# EEZ_DIB_MCU_r2B3.net
KiCad netlist of a schematic drawn in EAGLE
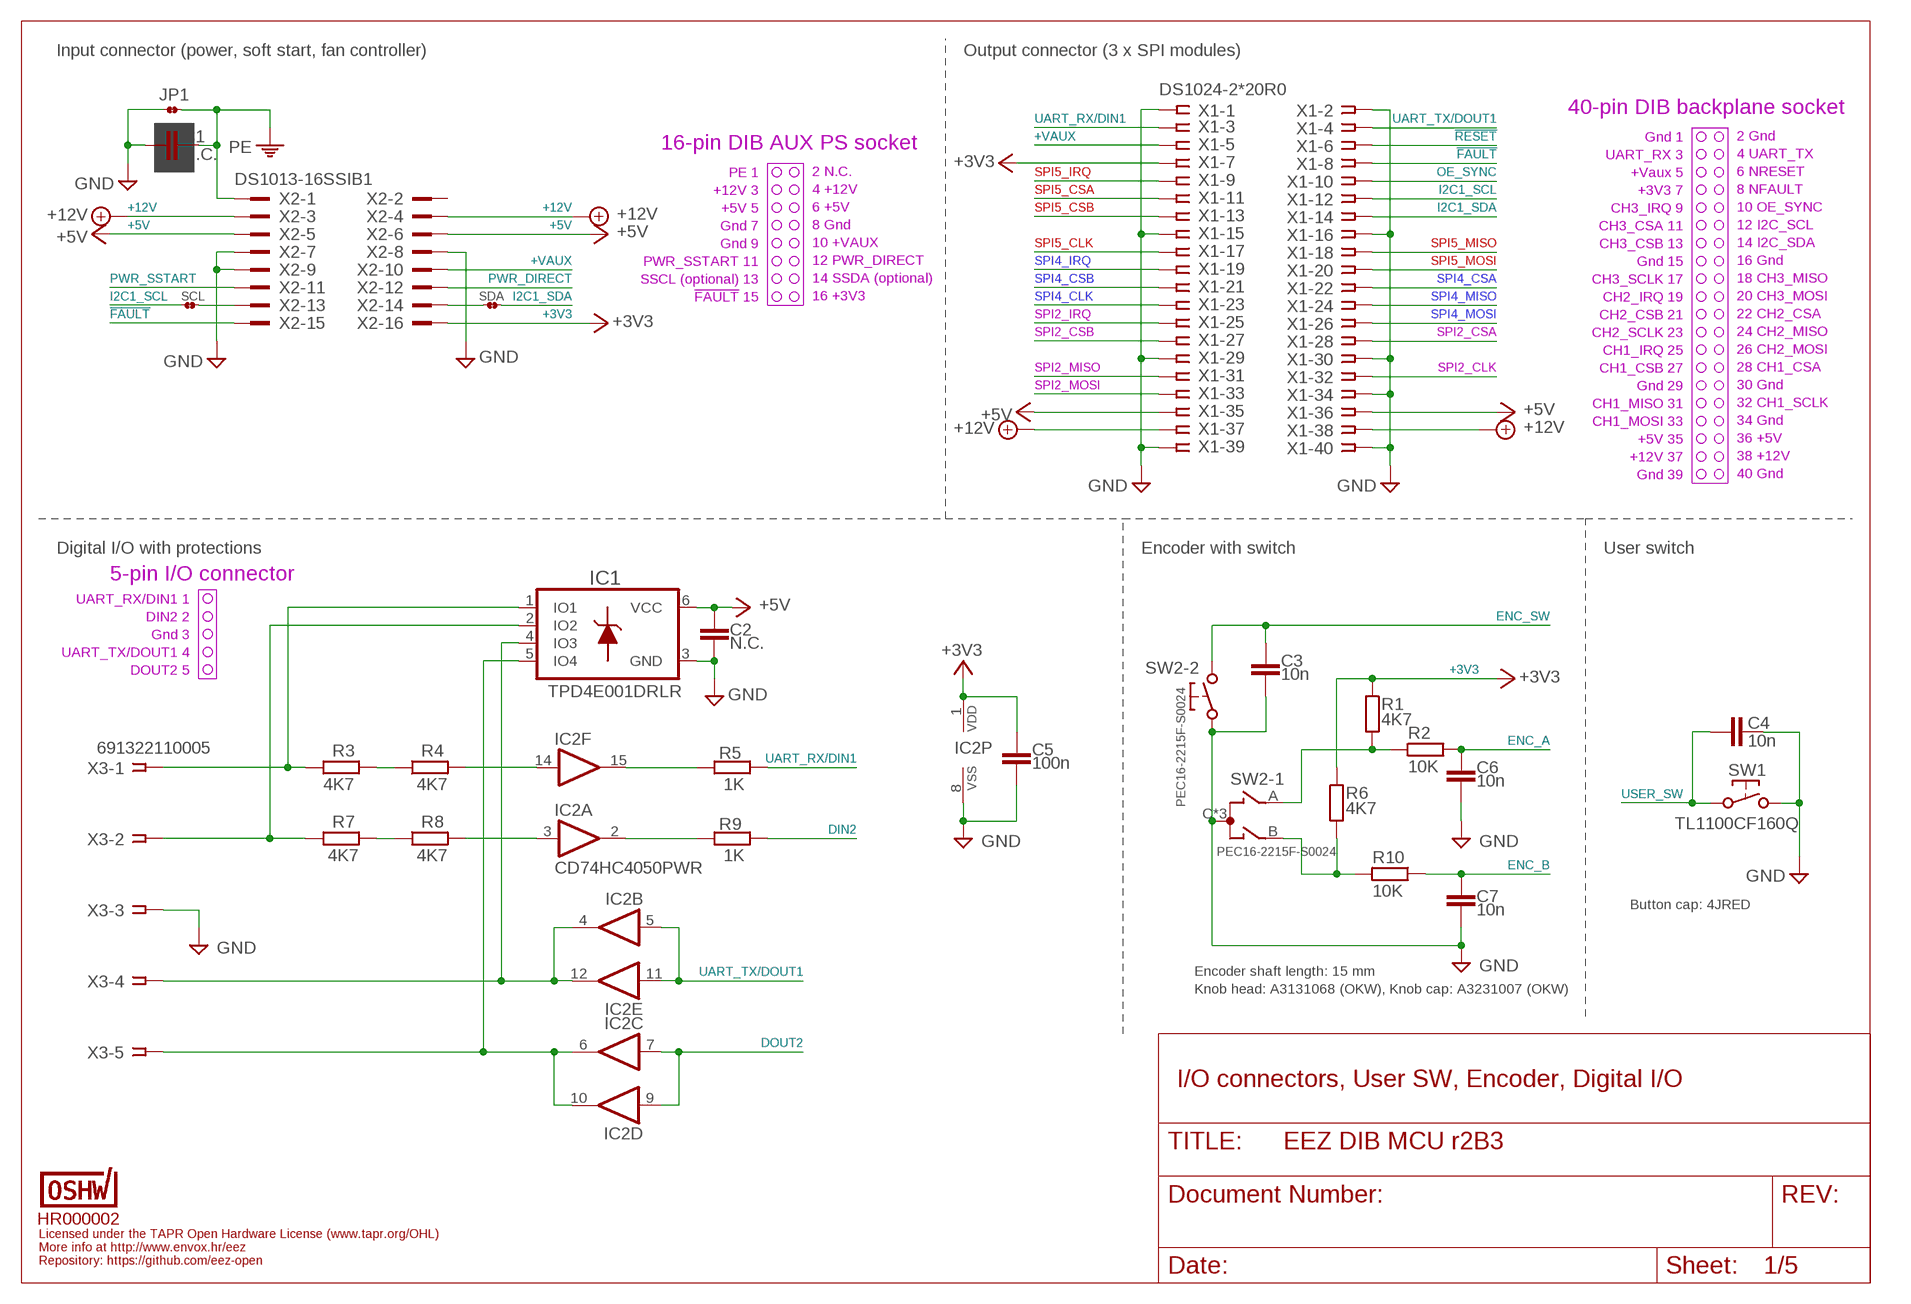
[diagram p0: schematic, sheet 1]
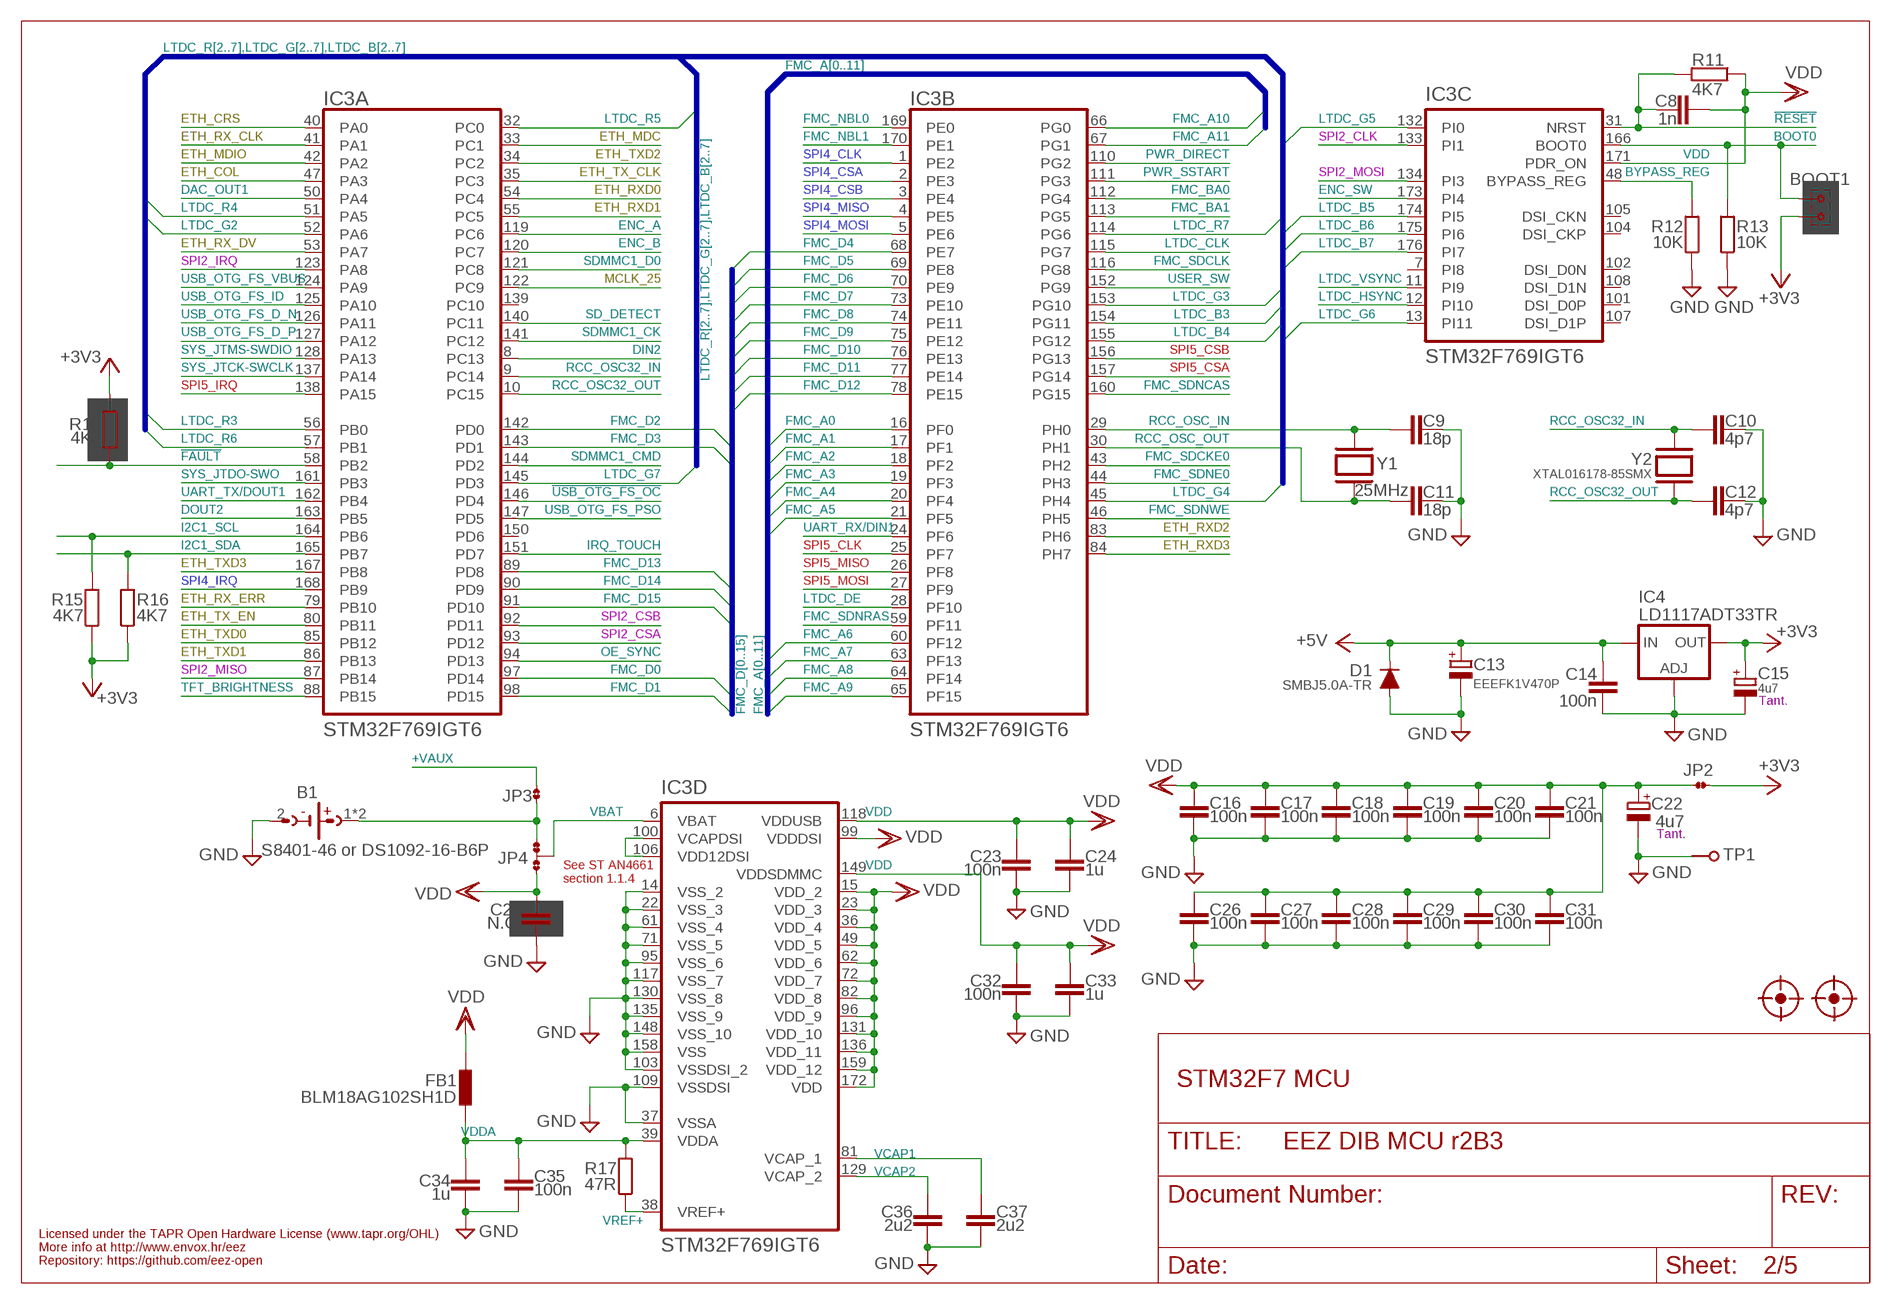
[diagram p1: schematic, sheet 2]
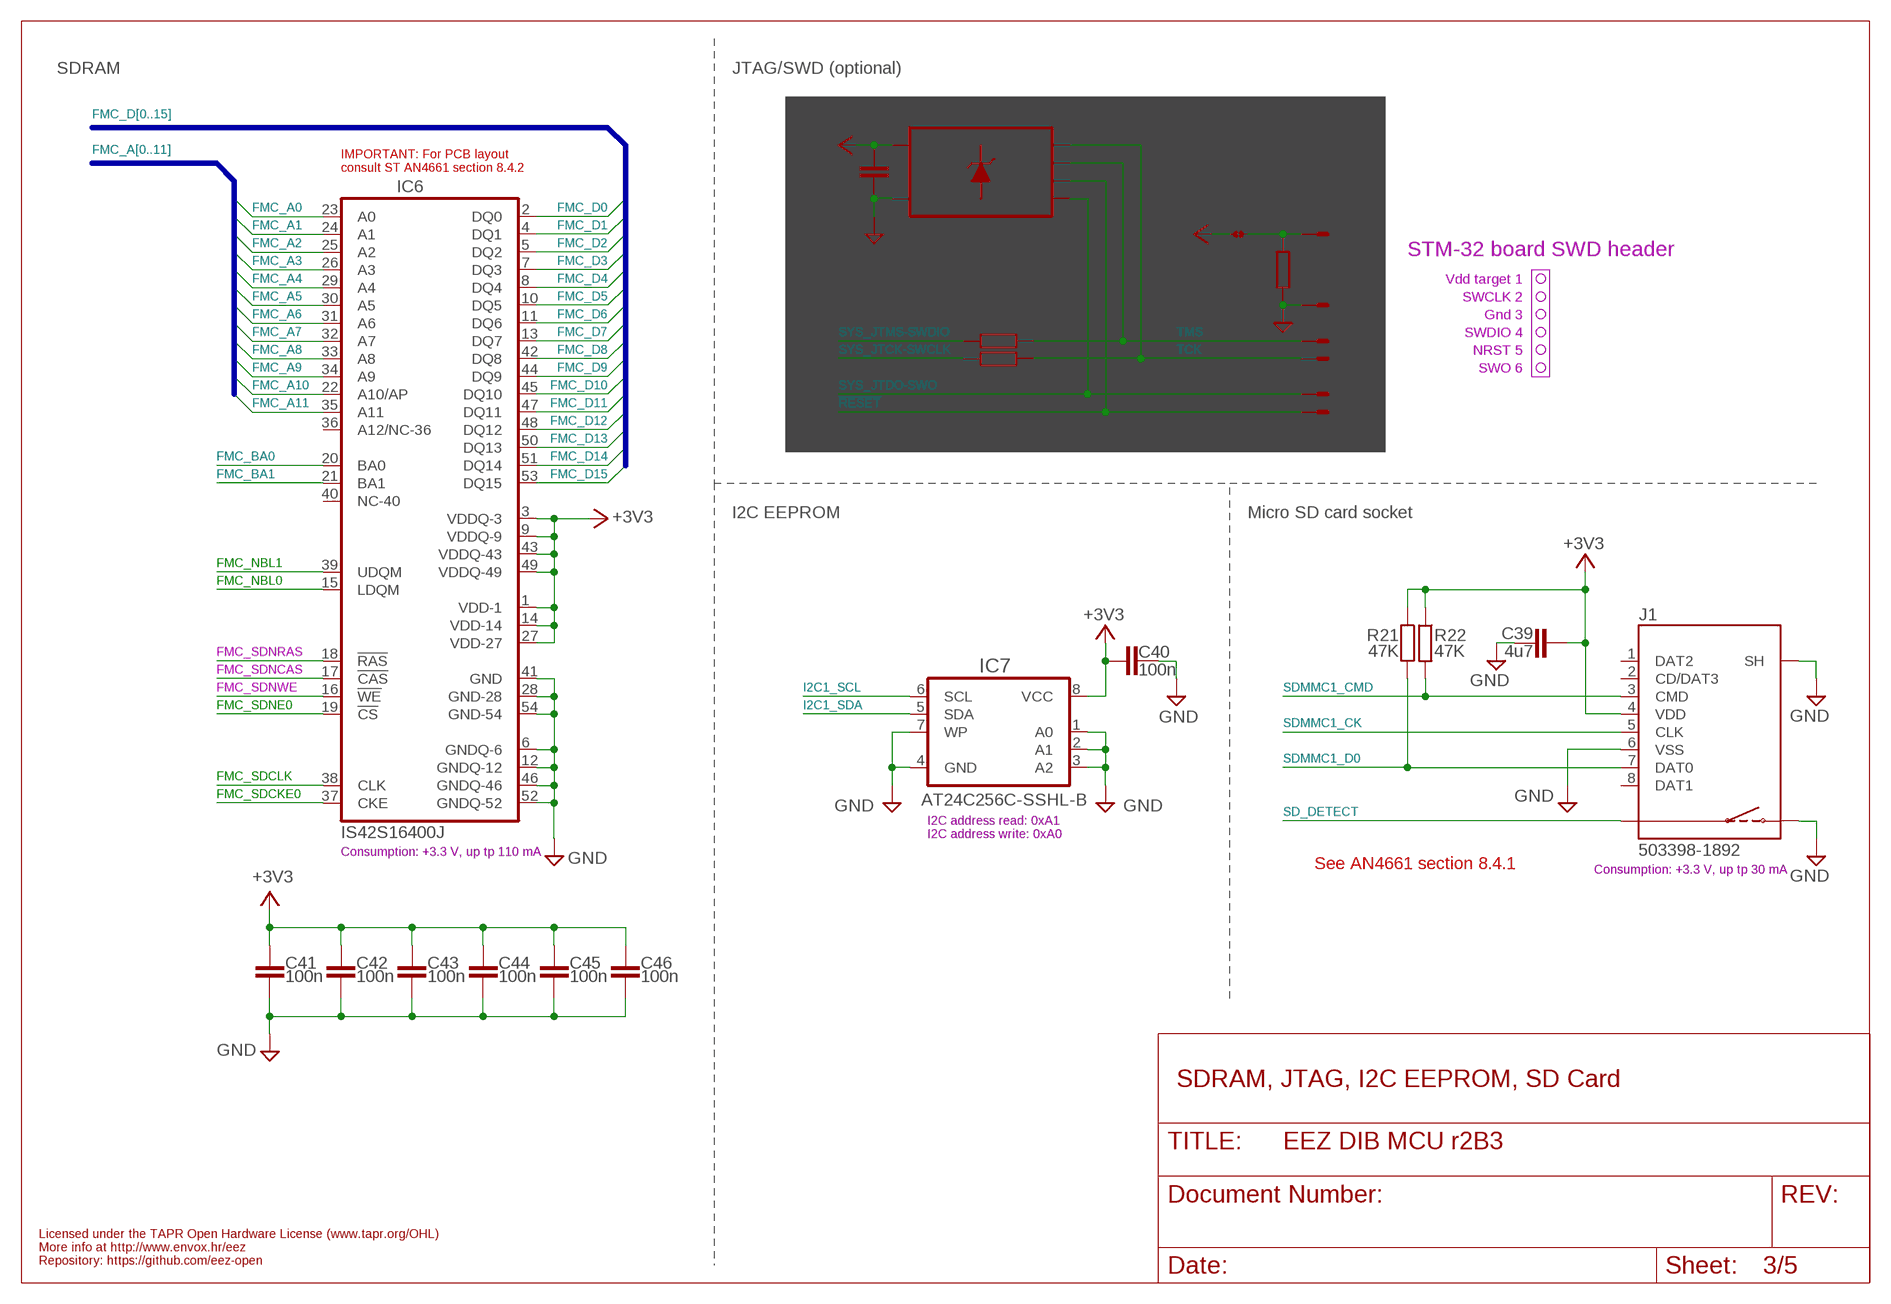
[diagram p2: schematic, sheet 3]
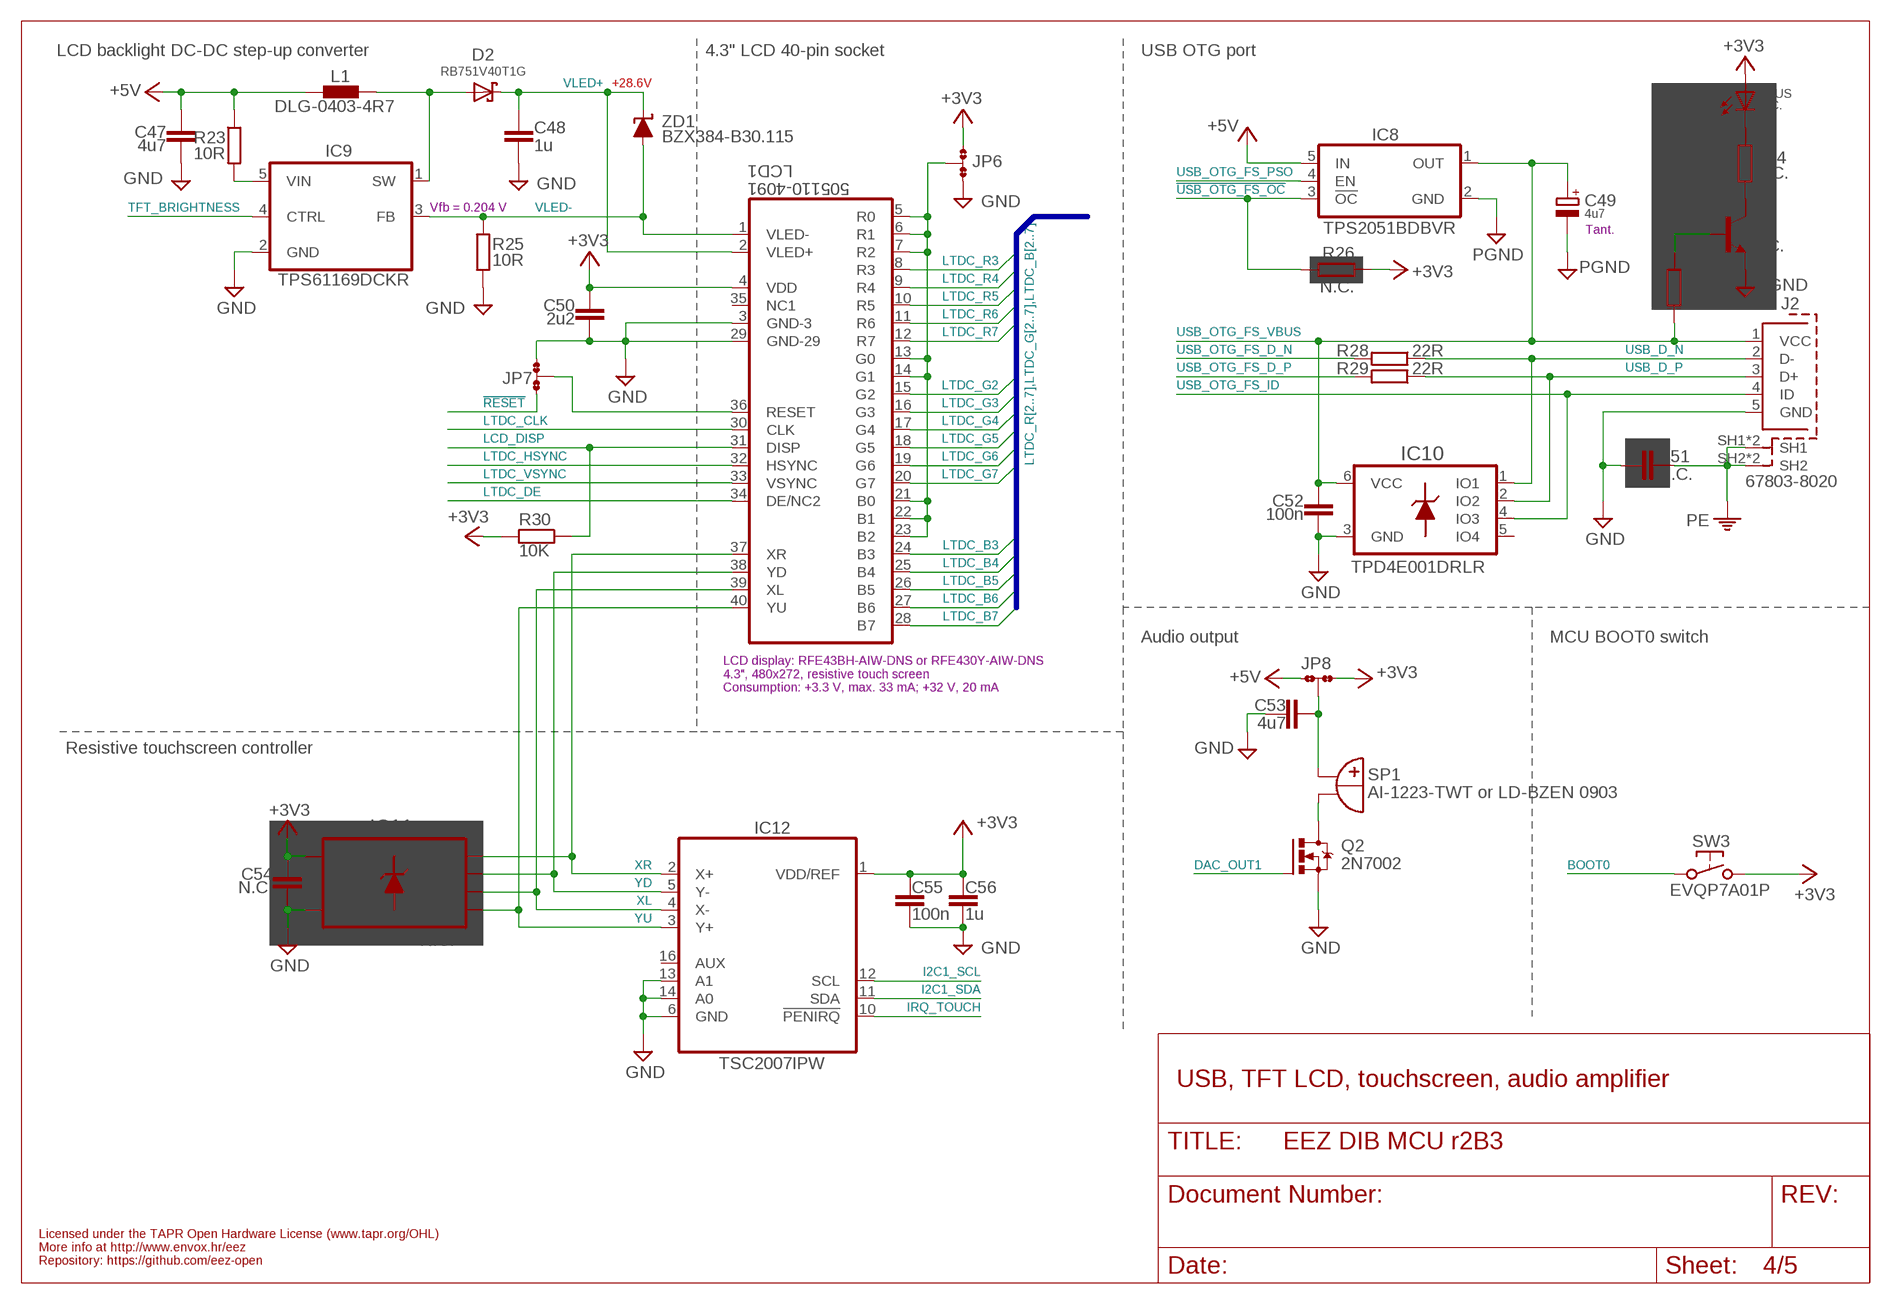
[diagram p3: schematic, sheet 4]
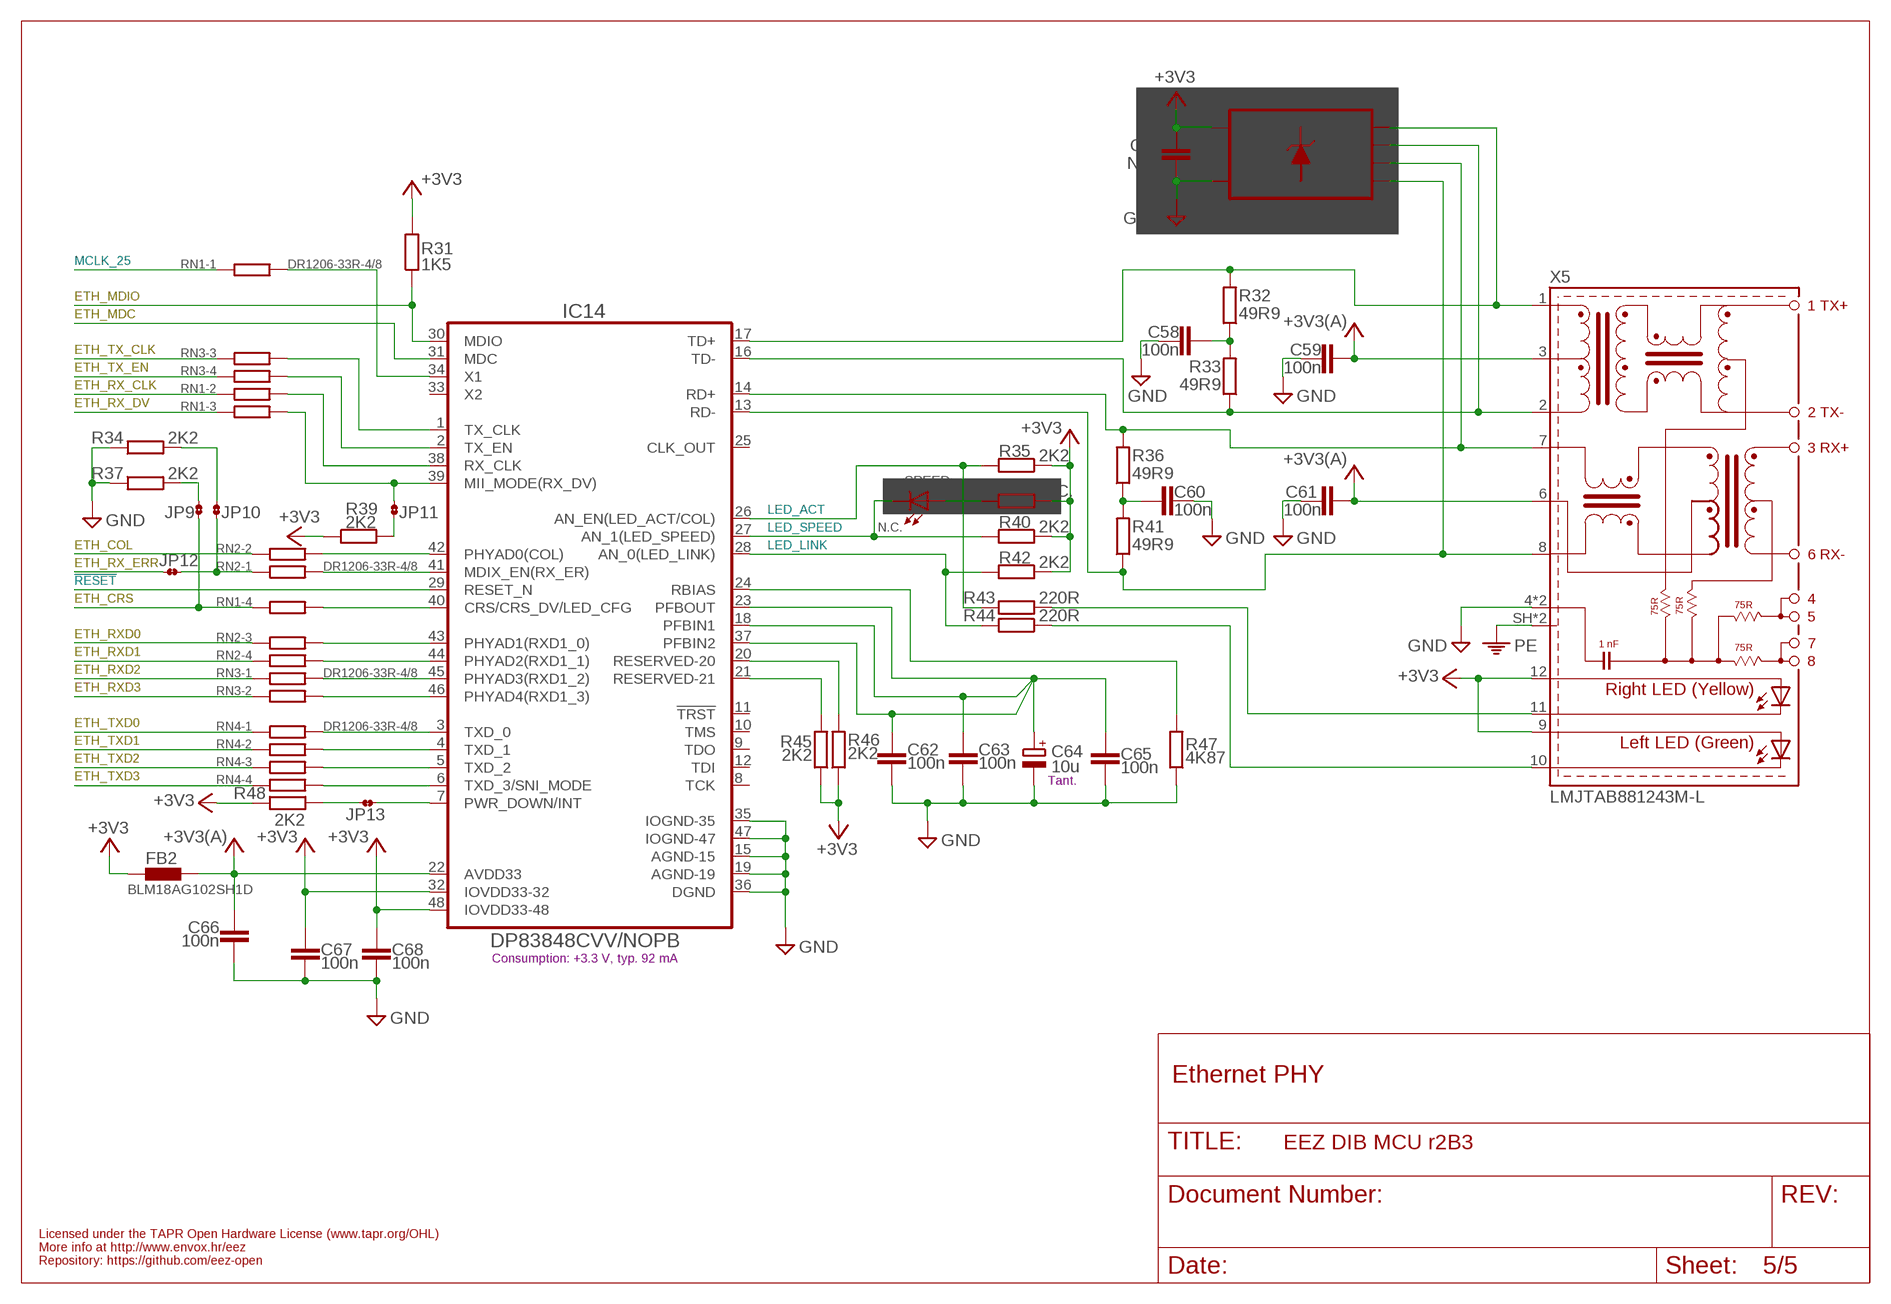
[diagram p4: schematic, sheet 5]

(export (version "E")
  (design (tool "Eeschema 10.0.6"))
  (components
    (comp (ref "C47")
      (value "4u7")
      (footprint "eagle-import:C1206")
      (libsource (lib "eagle-import") (part "C-EUC1206"))
    )
    (comp (ref "C48")
      (value "1u")
      (footprint "eagle-import:C0805")
      (libsource (lib "eagle-import") (part "C-EUC0805"))
    )
    (comp (ref "C49")
      (value "4u7")
      (footprint "eagle-import:EC1206")
      (libsource (lib "eagle-import") (part "ECAP1206"))
    )
    (comp (ref "C50")
      (value "2u2")
      (footprint "eagle-import:C0805")
      (libsource (lib "eagle-import") (part "C-EUC0805"))
    )
    (comp (ref "C51")
      (value "N.C.")
      (footprint "eagle-import:C0805")
      (libsource (lib "eagle-import") (part "C-EUC0805"))
    )
    (comp (ref "C52")
      (value "100n")
      (footprint "eagle-import:C0603")
      (libsource (lib "eagle-import") (part "C-EUC0603"))
    )
    (comp (ref "C53")
      (value "4u7")
      (footprint "eagle-import:C1206")
      (libsource (lib "eagle-import") (part "C-EUC1206"))
    )
    (comp (ref "C54")
      (value "N.C.")
      (footprint "eagle-import:C0603")
      (libsource (lib "eagle-import") (part "C-EUC0603"))
    )
    (comp (ref "C55")
      (value "100n")
      (footprint "eagle-import:C0603")
      (libsource (lib "eagle-import") (part "C-EUC0603"))
    )
    (comp (ref "C56")
      (value "1u")
      (footprint "eagle-import:C0805")
      (libsource (lib "eagle-import") (part "C-EUC0805"))
    )
    (comp (ref "D2")
      (value "RB751V40T1G")
      (footprint "eagle-import:SOD323-R")
      (libsource (lib "eagle-import") (part "SCHOTTKYSOD-323R"))
    )
    (comp (ref "IC8")
      (value "TPS2051BDBVR")
      (footprint "eagle-import:DBV5")
      (libsource (lib "eagle-import") (part "TPS2051B"))
    )
    (comp (ref "IC9")
      (value "TPS61169DCKR")
      (footprint "eagle-import:DCK5")
      (fields (field (name "MANUFACTURER") "Texas Instruments"))
      (libsource (lib "eagle-import") (part "TPS61169DCKR"))
    )
    (comp (ref "IC10")
      (value "TPD4E001DRLR")
      (footprint "eagle-import:DRL6")
      (libsource (lib "eagle-import") (part "TPD4E001-DRL"))
    )
    (comp (ref "IC11")
      (value "N.C.")
      (footprint "eagle-import:DRL6")
      (libsource (lib "eagle-import") (part "TPD4E001-DRL"))
    )
    (comp (ref "IC12")
      (value "TSC2007IPW")
      (footprint "eagle-import:PW(R-PDSO-G16)")
      (libsource (lib "eagle-import") (part "TSC2007IPW"))
    )
    (comp (ref "J2")
      (value "67803-8020")
      (footprint "eagle-import:678038020")
      (libsource (lib "eagle-import") (part "678038020"))
    )
    (comp (ref "JP6")
      (value "JP3-CUT")
      (footprint "eagle-import:JP3-CUT")
      (libsource (lib "eagle-import") (part "JP3-CUT"))
    )
    (comp (ref "JP7")
      (value "JP3-CUT")
      (footprint "eagle-import:JP3-CUT")
      (libsource (lib "eagle-import") (part "JP3-CUT"))
    )
    (comp (ref "JP8")
      (value "JP3-CUT")
      (footprint "eagle-import:JP3-CUT")
      (libsource (lib "eagle-import") (part "JP3-CUT"))
    )
    (comp (ref "L1")
      (value "DLG-0403-4R7")
      (footprint "eagle-import:DE0403")
      (libsource (lib "eagle-import") (part "DE0403"))
    )
    (comp (ref "LCD1")
      (value "505110-4091")
      (footprint "eagle-import:FPC_40")
      (libsource (lib "eagle-import") (part "RFE430Y-AIW-DNS"))
    )
    (comp (ref "Q1")
      (value "N.C.")
      (footprint "eagle-import:SOT23-BEC")
      (libsource (lib "eagle-import") (part "-NPN-SOT23-BECMMBT5551LT1"))
    )
    (comp (ref "Q2")
      (value "2N7002")
      (footprint "eagle-import:SOT103P240X110-3N")
      (fields (field (name "MPN") "2N7002-7-F"))
      (libsource (lib "eagle-import") (part "2N7002"))
    )
    (comp (ref "R23")
      (value "10R")
      (footprint "eagle-import:R0805")
      (libsource (lib "eagle-import") (part "R-EU_R0805"))
    )
    (comp (ref "R24")
      (value "N.C.")
      (footprint "eagle-import:R0805")
      (libsource (lib "eagle-import") (part "R-EU_R0805"))
    )
    (comp (ref "R25")
      (value "10R")
      (footprint "eagle-import:R0805")
      (libsource (lib "eagle-import") (part "R-EU_R0805"))
    )
    (comp (ref "R26")
      (value "N.C.")
      (footprint "eagle-import:R0805")
      (libsource (lib "eagle-import") (part "R-EU_R0805"))
    )
    (comp (ref "R27")
      (value "N.C.")
      (footprint "eagle-import:R0805")
      (libsource (lib "eagle-import") (part "R-EU_R0805"))
    )
    (comp (ref "R28")
      (value "22R")
      (footprint "eagle-import:R0805")
      (libsource (lib "eagle-import") (part "R-EU_R0805"))
    )
    (comp (ref "R29")
      (value "22R")
      (footprint "eagle-import:R0805")
      (libsource (lib "eagle-import") (part "R-EU_R0805"))
    )
    (comp (ref "R30")
      (value "10K")
      (footprint "eagle-import:R0805")
      (libsource (lib "eagle-import") (part "R-EU_R0805"))
    )
    (comp (ref "SP1")
      (value "AI-1223-TWT or LD-BZEN 0903")
      (footprint "eagle-import:AI-1223-TWT_COMBO")
      (libsource (lib "eagle-import") (part "AI-1223-TWT-LDB0903"))
    )
    (comp (ref "SW3")
      (value "EVQP7A01P")
      (footprint "eagle-import:PANASONIC_EVQP")
      (libsource (lib "eagle-import") (part "EVQP7A01P"))
    )
    (comp (ref "VBUS")
      (value "N.C.")
      (footprint "eagle-import:LED_0805")
      (libsource (lib "eagle-import") (part "LED0805"))
    )
    (comp (ref "ZD1")
      (value "BZX384-B30.115")
      (footprint "eagle-import:SOD323-W")
      (libsource (lib "eagle-import") (part "ZENER-DIODESOD323"))
    )
    (comp (ref "C1")
      (value "N.C.")
      (footprint "eagle-import:C0805")
      (libsource (lib "eagle-import") (part "C-EUC0805"))
    )
    (comp (ref "C2")
      (value "N.C.")
      (footprint "eagle-import:C0603")
      (libsource (lib "eagle-import") (part "C-EUC0603"))
    )
    (comp (ref "C3")
      (value "10n")
      (footprint "eagle-import:C0805")
      (libsource (lib "eagle-import") (part "C-EUC0805"))
    )
    (comp (ref "C4")
      (value "10n")
      (footprint "eagle-import:C0805")
      (libsource (lib "eagle-import") (part "C-EUC0805"))
    )
    (comp (ref "C5")
      (value "100n")
      (footprint "eagle-import:C0603")
      (libsource (lib "eagle-import") (part "C-EUC0603"))
    )
    (comp (ref "C6")
      (value "10n")
      (footprint "eagle-import:C0805")
      (libsource (lib "eagle-import") (part "C-EUC0805"))
    )
    (comp (ref "C7")
      (value "10n")
      (footprint "eagle-import:C0805")
      (libsource (lib "eagle-import") (part "C-EUC0805"))
    )
    (comp (ref "IC1")
      (value "TPD4E001DRLR")
      (footprint "eagle-import:DRL6")
      (libsource (lib "eagle-import") (part "TPD4E001-DRL"))
    )
    (comp (ref "IC2")
      (value "CD74HC4050PWR")
      (footprint "eagle-import:PW16")
      (libsource (lib "eagle-import") (part "CD74HC4050PWR"))
    )
    (comp (ref "JP1")
      (value "JP2-NOCUT")
      (footprint "eagle-import:JP2-NOCUT")
      (libsource (lib "eagle-import") (part "JP2-NOCUT"))
    )
    (comp (ref "R1")
      (value "4K7")
      (footprint "eagle-import:R0805")
      (libsource (lib "eagle-import") (part "R-EU_R0805"))
    )
    (comp (ref "R2")
      (value "10K")
      (footprint "eagle-import:R0805")
      (libsource (lib "eagle-import") (part "R-EU_R0805"))
    )
    (comp (ref "R3")
      (value "4K7")
      (footprint "eagle-import:R0805")
      (libsource (lib "eagle-import") (part "R-EU_R0805"))
    )
    (comp (ref "R4")
      (value "4K7")
      (footprint "eagle-import:R0805")
      (libsource (lib "eagle-import") (part "R-EU_R0805"))
    )
    (comp (ref "R5")
      (value "1K")
      (footprint "eagle-import:R0805")
      (libsource (lib "eagle-import") (part "R-EU_R0805"))
    )
    (comp (ref "R6")
      (value "4K7")
      (footprint "eagle-import:R0805")
      (libsource (lib "eagle-import") (part "R-EU_R0805"))
    )
    (comp (ref "R7")
      (value "4K7")
      (footprint "eagle-import:R0805")
      (libsource (lib "eagle-import") (part "R-EU_R0805"))
    )
    (comp (ref "R8")
      (value "4K7")
      (footprint "eagle-import:R0805")
      (libsource (lib "eagle-import") (part "R-EU_R0805"))
    )
    (comp (ref "R9")
      (value "1K")
      (footprint "eagle-import:R0805")
      (libsource (lib "eagle-import") (part "R-EU_R0805"))
    )
    (comp (ref "R10")
      (value "10K")
      (footprint "eagle-import:R0805")
      (libsource (lib "eagle-import") (part "R-EU_R0805"))
    )
    (comp (ref "SCL")
      (value "JP2-NOCUT")
      (footprint "eagle-import:JP2-NOCUT")
      (libsource (lib "eagle-import") (part "JP2-NOCUT"))
    )
    (comp (ref "SDA")
      (value "JP2-NOCUT")
      (footprint "eagle-import:JP2-NOCUT")
      (libsource (lib "eagle-import") (part "JP2-NOCUT"))
    )
    (comp (ref "SW1")
      (value "TL1100CF160Q")
      (footprint "eagle-import:TL1100C")
      (libsource (lib "eagle-import") (part "TL1100C"))
    )
    (comp (ref "SW2")
      (value "PEC16-2215F-S0024")
      (footprint "eagle-import:PEC16-2215F")
      (libsource (lib "eagle-import") (part "ENCODER_SW-PEC16"))
    )
    (comp (ref "U$3")
      (value "HR000002")
      (footprint "eagle-import:CERT-SMALL-SILK")
      (libsource (lib "eagle-import") (part "CERT-SMALL"))
    )
    (comp (ref "X1")
      (value "DS1024-2*20R0")
      (footprint "eagle-import:ZL263-40DG")
      (libsource (lib "eagle-import") (part "ZL263-40DG"))
    )
    (comp (ref "X2")
      (value "DS1013-16SSIB1")
      (footprint "eagle-import:IDC-16PIN")
      (libsource (lib "eagle-import") (part "IDC-16PIN"))
    )
    (comp (ref "X3")
      (value "691322110005")
      (footprint "eagle-import:MC1,5_5-G-3,5")
      (libsource (lib "eagle-import") (part "MC1,5/5-G-3,5"))
    )
    (comp (ref "C38")
      (value "N.C.")
      (footprint "eagle-import:C0603")
      (libsource (lib "eagle-import") (part "C-EUC0603"))
    )
    (comp (ref "C39")
      (value "4u7")
      (footprint "eagle-import:C1206")
      (libsource (lib "eagle-import") (part "C-EUC1206"))
    )
    (comp (ref "C40")
      (value "100n")
      (footprint "eagle-import:C0603")
      (libsource (lib "eagle-import") (part "C-EUC0603"))
    )
    (comp (ref "C41")
      (value "100n")
      (footprint "eagle-import:C0603")
      (libsource (lib "eagle-import") (part "C-EUC0603"))
    )
    (comp (ref "C42")
      (value "100n")
      (footprint "eagle-import:C0603")
      (libsource (lib "eagle-import") (part "C-EUC0603"))
    )
    (comp (ref "C43")
      (value "100n")
      (footprint "eagle-import:C0603")
      (libsource (lib "eagle-import") (part "C-EUC0603"))
    )
    (comp (ref "C44")
      (value "100n")
      (footprint "eagle-import:C0603")
      (libsource (lib "eagle-import") (part "C-EUC0603"))
    )
    (comp (ref "C45")
      (value "100n")
      (footprint "eagle-import:C0603")
      (libsource (lib "eagle-import") (part "C-EUC0603"))
    )
    (comp (ref "C46")
      (value "100n")
      (footprint "eagle-import:C0603")
      (libsource (lib "eagle-import") (part "C-EUC0603"))
    )
    (comp (ref "IC5")
      (value "N.C.")
      (footprint "eagle-import:DRL6")
      (libsource (lib "eagle-import") (part "TPD4E001-DRL"))
    )
    (comp (ref "IC6")
      (value "IS42S16400J")
      (footprint "eagle-import:TSOPII-54")
      (libsource (lib "eagle-import") (part "IS42S16400"))
    )
    (comp (ref "IC7")
      (value "AT24C256C-SSHL-B")
      (footprint "eagle-import:SOIC127P600X173-8N")
      (libsource (lib "eagle-import") (part "AT24CXXSOIC8"))
    )
    (comp (ref "J1")
      (value "503398-1892")
      (footprint "eagle-import:5033981892")
      (libsource (lib "eagle-import") (part "5033981892"))
    )
    (comp (ref "JP5")
      (value "JP2-CUT")
      (footprint "eagle-import:JP2-CUT")
      (libsource (lib "eagle-import") (part "JP2-CUT"))
    )
    (comp (ref "R18")
      (value "N.C.")
      (footprint "eagle-import:R0805")
      (libsource (lib "eagle-import") (part "R-EU_R0805"))
    )
    (comp (ref "R19")
      (value "N.C.")
      (footprint "eagle-import:R0805")
      (libsource (lib "eagle-import") (part "R-EU_R0805"))
    )
    (comp (ref "R20")
      (value "N.C.")
      (footprint "eagle-import:R0805")
      (libsource (lib "eagle-import") (part "R-EU_R0805"))
    )
    (comp (ref "R21")
      (value "47K")
      (footprint "eagle-import:R0805")
      (libsource (lib "eagle-import") (part "R-EU_R0805"))
    )
    (comp (ref "R22")
      (value "47K")
      (footprint "eagle-import:R0805")
      (libsource (lib "eagle-import") (part "R-EU_R0805"))
    )
    (comp (ref "X4")
      (value "N.C.")
      (footprint "eagle-import:22-23-2061")
      (fields (field (name "MF") "MOLEX") (field (name "MPN") "22-23-2061"))
      (libsource (lib "eagle-import") (part "22-23-2061"))
    )
    (comp (ref "B1")
      (value "S8401-46 or DS1092-16-B6P")
      (footprint "eagle-import:S8401-46")
      (libsource (lib "eagle-import") (part "CELL_BATTERYVERT"))
    )
    (comp (ref "BOOT1")
      (value "JUMPER-2PIN-2MM")
      (footprint "eagle-import:2MM-2")
      (libsource (lib "eagle-import") (part "JUMPER-2PIN-2MM"))
    )
    (comp (ref "C8")
      (value "1n")
      (footprint "eagle-import:C0805")
      (libsource (lib "eagle-import") (part "C-EUC0805"))
    )
    (comp (ref "C9")
      (value "18p")
      (footprint "eagle-import:C0603")
      (libsource (lib "eagle-import") (part "C-EUC0603"))
    )
    (comp (ref "C10")
      (value "4p7")
      (footprint "eagle-import:C0603")
      (libsource (lib "eagle-import") (part "C-EUC0603"))
    )
    (comp (ref "C11")
      (value "18p")
      (footprint "eagle-import:C0603")
      (libsource (lib "eagle-import") (part "C-EUC0603"))
    )
    (comp (ref "C12")
      (value "4p7")
      (footprint "eagle-import:C0603")
      (libsource (lib "eagle-import") (part "C-EUC0603"))
    )
    (comp (ref "C13")
      (value "EEEFK1V470P")
      (footprint "eagle-import:CAPAE660X610N")
      (libsource (lib "eagle-import") (part "ECAPPANASONIC_H"))
    )
    (comp (ref "C14")
      (value "100n")
      (footprint "eagle-import:C0603")
      (libsource (lib "eagle-import") (part "C-EUC0603"))
    )
    (comp (ref "C15")
      (value "4u7")
      (footprint "eagle-import:EC1206")
      (libsource (lib "eagle-import") (part "ECAP1206"))
    )
    (comp (ref "C16")
      (value "100n")
      (footprint "eagle-import:C0603")
      (libsource (lib "eagle-import") (part "C-EUC0603"))
    )
    (comp (ref "C17")
      (value "100n")
      (footprint "eagle-import:C0603")
      (libsource (lib "eagle-import") (part "C-EUC0603"))
    )
    (comp (ref "C18")
      (value "100n")
      (footprint "eagle-import:C0603")
      (libsource (lib "eagle-import") (part "C-EUC0603"))
    )
    (comp (ref "C19")
      (value "100n")
      (footprint "eagle-import:C0603")
      (libsource (lib "eagle-import") (part "C-EUC0603"))
    )
    (comp (ref "C20")
      (value "100n")
      (footprint "eagle-import:C0603")
      (libsource (lib "eagle-import") (part "C-EUC0603"))
    )
    (comp (ref "C21")
      (value "100n")
      (footprint "eagle-import:C0603")
      (libsource (lib "eagle-import") (part "C-EUC0603"))
    )
    (comp (ref "C22")
      (value "4u7")
      (footprint "eagle-import:EC1206")
      (libsource (lib "eagle-import") (part "ECAP1206"))
    )
    (comp (ref "C23")
      (value "100n")
      (footprint "eagle-import:C0603")
      (libsource (lib "eagle-import") (part "C-EUC0603"))
    )
    (comp (ref "C24")
      (value "1u")
      (footprint "eagle-import:C0805")
      (libsource (lib "eagle-import") (part "C-EUC0805"))
    )
    (comp (ref "C25")
      (value "N.C.")
      (footprint "eagle-import:C0603")
      (libsource (lib "eagle-import") (part "C-EUC0603"))
    )
    (comp (ref "C26")
      (value "100n")
      (footprint "eagle-import:C0603")
      (libsource (lib "eagle-import") (part "C-EUC0603"))
    )
    (comp (ref "C27")
      (value "100n")
      (footprint "eagle-import:C0603")
      (libsource (lib "eagle-import") (part "C-EUC0603"))
    )
    (comp (ref "C28")
      (value "100n")
      (footprint "eagle-import:C0603")
      (libsource (lib "eagle-import") (part "C-EUC0603"))
    )
    (comp (ref "C29")
      (value "100n")
      (footprint "eagle-import:C0603")
      (libsource (lib "eagle-import") (part "C-EUC0603"))
    )
    (comp (ref "C30")
      (value "100n")
      (footprint "eagle-import:C0603")
      (libsource (lib "eagle-import") (part "C-EUC0603"))
    )
    (comp (ref "C31")
      (value "100n")
      (footprint "eagle-import:C0603")
      (libsource (lib "eagle-import") (part "C-EUC0603"))
    )
    (comp (ref "C32")
      (value "100n")
      (footprint "eagle-import:C0603")
      (libsource (lib "eagle-import") (part "C-EUC0603"))
    )
    (comp (ref "C33")
      (value "1u")
      (footprint "eagle-import:C0805")
      (libsource (lib "eagle-import") (part "C-EUC0805"))
    )
    (comp (ref "C34")
      (value "1u")
      (footprint "eagle-import:C0805")
      (libsource (lib "eagle-import") (part "C-EUC0805"))
    )
    (comp (ref "C35")
      (value "100n")
      (footprint "eagle-import:C0603")
      (libsource (lib "eagle-import") (part "C-EUC0603"))
    )
    (comp (ref "C36")
      (value "2u2")
      (footprint "eagle-import:C0805")
      (libsource (lib "eagle-import") (part "C-EUC0805"))
    )
    (comp (ref "C37")
      (value "2u2")
      (footprint "eagle-import:C0805")
      (libsource (lib "eagle-import") (part "C-EUC0805"))
    )
    (comp (ref "D1")
      (value "SMBJ5.0A-TR")
      (footprint "eagle-import:DO214AA")
      (libsource (lib "eagle-import") (part "DIODEDO214AA"))
    )
    (comp (ref "FB1")
      (value "BLM18AG102SH1D")
      (footprint "eagle-import:BEAD0603")
      (libsource (lib "eagle-import") (part "FERRITE_BEAD0603"))
    )
    (comp (ref "FM1")
      (value "FIDUCIAL")
      (footprint "eagle-import:FIDUCIAL")
      (libsource (lib "eagle-import") (part "FIDUCIAL"))
    )
    (comp (ref "FM2")
      (value "FIDUCIAL")
      (footprint "eagle-import:FIDUCIAL")
      (libsource (lib "eagle-import") (part "FIDUCIAL"))
    )
    (comp (ref "IC3")
      (value "STM32F769IGT6")
      (footprint "eagle-import:LQFP-176_24X24MM")
      (fields
        (field (name "MANUFACTURER_PART_NUMBER") "stm32f769ixt")
        (field (name "COPYRIGHT") "Copyright C 2016 Accelerated Designs. All rights reserved")
      )
      (libsource (lib "eagle-import") (part "STM32F769IXT"))
    )
    (comp (ref "IC4")
      (value "LD1117ADT33TR")
      (footprint "eagle-import:DPACK")
      (libsource (lib "eagle-import") (part "LD117A?DT33TR"))
    )
    (comp (ref "JP2")
      (value "JP2-NOCUT")
      (footprint "eagle-import:JP2-NOCUT")
      (libsource (lib "eagle-import") (part "JP2-NOCUT"))
    )
    (comp (ref "JP3")
      (value "JP2-CUT")
      (footprint "eagle-import:JP2-CUT")
      (libsource (lib "eagle-import") (part "JP2-CUT"))
    )
    (comp (ref "JP4")
      (value "JP3-CUT")
      (footprint "eagle-import:JP3-CUT")
      (libsource (lib "eagle-import") (part "JP3-CUT"))
    )
    (comp (ref "R11")
      (value "4K7")
      (footprint "eagle-import:R0805")
      (libsource (lib "eagle-import") (part "R-EU_R0805"))
    )
    (comp (ref "R12")
      (value "10K")
      (footprint "eagle-import:R0805")
      (libsource (lib "eagle-import") (part "R-EU_R0805"))
    )
    (comp (ref "R13")
      (value "10K")
      (footprint "eagle-import:R0805")
      (libsource (lib "eagle-import") (part "R-EU_R0805"))
    )
    (comp (ref "R14")
      (value "4K7")
      (footprint "eagle-import:R0805")
      (libsource (lib "eagle-import") (part "R-EU_R0805"))
    )
    (comp (ref "R15")
      (value "4K7")
      (footprint "eagle-import:R0805")
      (libsource (lib "eagle-import") (part "R-EU_R0805"))
    )
    (comp (ref "R16")
      (value "4K7")
      (footprint "eagle-import:R0805")
      (libsource (lib "eagle-import") (part "R-EU_R0805"))
    )
    (comp (ref "R17")
      (value "47R")
      (footprint "eagle-import:R0805")
      (libsource (lib "eagle-import") (part "R-EU_R0805"))
    )
    (comp (ref "TP1")
      (value "PCB_TEST_TABSHIELD")
      (footprint "eagle-import:PCB_SHIELD_TAB")
      (libsource (lib "eagle-import") (part "PCB_TEST_TABSHIELD"))
    )
    (comp (ref "Y1")
      (value "25MHz")
      (footprint "eagle-import:HC-49_4H")
      (libsource (lib "eagle-import") (part "XTALSMD"))
    )
    (comp (ref "Y2")
      (value "XTAL016178-85SMX")
      (footprint "eagle-import:85SMX")
      (libsource (lib "eagle-import") (part "XTAL85SMX"))
    )
    (comp (ref "C57")
      (value "N.C.")
      (footprint "eagle-import:C0603")
      (libsource (lib "eagle-import") (part "C-EUC0603"))
    )
    (comp (ref "C58")
      (value "100n")
      (footprint "eagle-import:C0603")
      (libsource (lib "eagle-import") (part "C-EUC0603"))
    )
    (comp (ref "C59")
      (value "100n")
      (footprint "eagle-import:C0603")
      (libsource (lib "eagle-import") (part "C-EUC0603"))
    )
    (comp (ref "C60")
      (value "100n")
      (footprint "eagle-import:C0603")
      (libsource (lib "eagle-import") (part "C-EUC0603"))
    )
    (comp (ref "C61")
      (value "100n")
      (footprint "eagle-import:C0603")
      (libsource (lib "eagle-import") (part "C-EUC0603"))
    )
    (comp (ref "C62")
      (value "100n")
      (footprint "eagle-import:C0603")
      (libsource (lib "eagle-import") (part "C-EUC0603"))
    )
    (comp (ref "C63")
      (value "100n")
      (footprint "eagle-import:C0603")
      (libsource (lib "eagle-import") (part "C-EUC0603"))
    )
    (comp (ref "C64")
      (value "10u")
      (footprint "eagle-import:EC1206")
      (libsource (lib "eagle-import") (part "ECAP1206"))
    )
    (comp (ref "C65")
      (value "100n")
      (footprint "eagle-import:C0603")
      (libsource (lib "eagle-import") (part "C-EUC0603"))
    )
    (comp (ref "C66")
      (value "100n")
      (footprint "eagle-import:C0603")
      (libsource (lib "eagle-import") (part "C-EUC0603"))
    )
    (comp (ref "C67")
      (value "100n")
      (footprint "eagle-import:C0603")
      (libsource (lib "eagle-import") (part "C-EUC0603"))
    )
    (comp (ref "C68")
      (value "100n")
      (footprint "eagle-import:C0603")
      (libsource (lib "eagle-import") (part "C-EUC0603"))
    )
    (comp (ref "FB2")
      (value "BLM18AG102SH1D")
      (footprint "eagle-import:BEAD0603")
      (libsource (lib "eagle-import") (part "FERRITE_BEAD0603"))
    )
    (comp (ref "IC13")
      (value "N.C.")
      (footprint "eagle-import:DRL6")
      (libsource (lib "eagle-import") (part "TPD4E001-DRL"))
    )
    (comp (ref "IC14")
      (value "DP83848CVV/NOPB")
      (footprint "eagle-import:PT48")
      (libsource (lib "eagle-import") (part "DP83848CVV/NOPB"))
    )
    (comp (ref "JP9")
      (value "JP2-CUT")
      (footprint "eagle-import:JP2-CUT")
      (libsource (lib "eagle-import") (part "JP2-CUT"))
    )
    (comp (ref "JP10")
      (value "JP2-CUT")
      (footprint "eagle-import:JP2-CUT")
      (libsource (lib "eagle-import") (part "JP2-CUT"))
    )
    (comp (ref "JP11")
      (value "JP2-CUT")
      (footprint "eagle-import:JP2-CUT")
      (libsource (lib "eagle-import") (part "JP2-CUT"))
    )
    (comp (ref "JP12")
      (value "JP2-NOCUT")
      (footprint "eagle-import:JP2-NOCUT")
      (libsource (lib "eagle-import") (part "JP2-NOCUT"))
    )
    (comp (ref "JP13")
      (value "JP2-NOCUT")
      (footprint "eagle-import:JP2-NOCUT")
      (libsource (lib "eagle-import") (part "JP2-NOCUT"))
    )
    (comp (ref "R31")
      (value "1K5")
      (footprint "eagle-import:R0805")
      (libsource (lib "eagle-import") (part "R-EU_R0805"))
    )
    (comp (ref "R32")
      (value "49R9")
      (footprint "eagle-import:R0805")
      (libsource (lib "eagle-import") (part "R-EU_R0805"))
    )
    (comp (ref "R33")
      (value "49R9")
      (footprint "eagle-import:R0805")
      (libsource (lib "eagle-import") (part "R-EU_R0805"))
    )
    (comp (ref "R34")
      (value "2K2")
      (footprint "eagle-import:R0805")
      (libsource (lib "eagle-import") (part "R-EU_R0805"))
    )
    (comp (ref "R35")
      (value "2K2")
      (footprint "eagle-import:R0805")
      (libsource (lib "eagle-import") (part "R-EU_R0805"))
    )
    (comp (ref "R36")
      (value "49R9")
      (footprint "eagle-import:R0805")
      (libsource (lib "eagle-import") (part "R-EU_R0805"))
    )
    (comp (ref "R37")
      (value "2K2")
      (footprint "eagle-import:R0805")
      (libsource (lib "eagle-import") (part "R-EU_R0805"))
    )
    (comp (ref "R38")
      (value "N.C.")
      (footprint "eagle-import:R0805")
      (libsource (lib "eagle-import") (part "R-EU_R0805"))
    )
    (comp (ref "R39")
      (value "2K2")
      (footprint "eagle-import:R0805")
      (libsource (lib "eagle-import") (part "R-EU_R0805"))
    )
    (comp (ref "R40")
      (value "2K2")
      (footprint "eagle-import:R0805")
      (libsource (lib "eagle-import") (part "R-EU_R0805"))
    )
    (comp (ref "R41")
      (value "49R9")
      (footprint "eagle-import:R0805")
      (libsource (lib "eagle-import") (part "R-EU_R0805"))
    )
    (comp (ref "R42")
      (value "2K2")
      (footprint "eagle-import:R0805")
      (libsource (lib "eagle-import") (part "R-EU_R0805"))
    )
    (comp (ref "R43")
      (value "220R")
      (footprint "eagle-import:R0805")
      (libsource (lib "eagle-import") (part "R-EU_R0805"))
    )
    (comp (ref "R44")
      (value "220R")
      (footprint "eagle-import:R0805")
      (libsource (lib "eagle-import") (part "R-EU_R0805"))
    )
    (comp (ref "R45")
      (value "2K2")
      (footprint "eagle-import:R0805")
      (libsource (lib "eagle-import") (part "R-EU_R0805"))
    )
    (comp (ref "R46")
      (value "2K2")
      (footprint "eagle-import:R0805")
      (libsource (lib "eagle-import") (part "R-EU_R0805"))
    )
    (comp (ref "R47")
      (value "4K87")
      (footprint "eagle-import:R0805")
      (libsource (lib "eagle-import") (part "R-EU_R0805"))
    )
    (comp (ref "R48")
      (value "2K2")
      (footprint "eagle-import:R0805")
      (libsource (lib "eagle-import") (part "R-EU_R0805"))
    )
    (comp (ref "RN1")
      (value "DR1206-33R-4/8")
      (footprint "eagle-import:CAY16")
      (libsource (lib "eagle-import") (part "R_ARRAY4"))
    )
    (comp (ref "RN2")
      (value "DR1206-33R-4/8")
      (footprint "eagle-import:CAY16")
      (libsource (lib "eagle-import") (part "R_ARRAY4"))
    )
    (comp (ref "RN3")
      (value "DR1206-33R-4/8")
      (footprint "eagle-import:CAY16")
      (libsource (lib "eagle-import") (part "R_ARRAY4"))
    )
    (comp (ref "RN4")
      (value "DR1206-33R-4/8")
      (footprint "eagle-import:CAY16")
      (libsource (lib "eagle-import") (part "R_ARRAY4"))
    )
    (comp (ref "SPEED")
      (value "N.C.")
      (footprint "eagle-import:LED_0805")
      (libsource (lib "eagle-import") (part "LED0805"))
    )
    (comp (ref "X5")
      (value "LMJTAB881243M-L")
      (footprint "eagle-import:RJ45-TRAFO-LED")
      (libsource (lib "eagle-import") (part "RJ45-TRAFO-LED"))
    )
  )
  (nets
    (net (code "1") (name "+3V3") (class "Default")
      (node (ref "BOOT1") (pin "2") (pinfunction "2_2") (pintype "passive"))
      (node (ref "C15") (pin "+") (pinfunction "+_+") (pintype "passive"))
      (node (ref "C38") (pin "1") (pinfunction "1_1") (pintype "passive"))
      (node (ref "C39") (pin "1") (pinfunction "1_1") (pintype "passive"))
      (node (ref "C40") (pin "2") (pinfunction "2_2") (pintype "passive"))
      (node (ref "C41") (pin "1") (pinfunction "1_1") (pintype "passive"))
      (node (ref "C42") (pin "1") (pinfunction "1_1") (pintype "passive"))
      (node (ref "C43") (pin "1") (pinfunction "1_1") (pintype "passive"))
      (node (ref "C44") (pin "1") (pinfunction "1_1") (pintype "passive"))
      (node (ref "C45") (pin "1") (pinfunction "1_1") (pintype "passive"))
      (node (ref "C46") (pin "1") (pinfunction "1_1") (pintype "passive"))
      (node (ref "C5") (pin "1") (pinfunction "1_1") (pintype "passive"))
      (node (ref "C50") (pin "1") (pinfunction "1_1") (pintype "passive"))
      (node (ref "C54") (pin "2") (pinfunction "2_2") (pintype "passive"))
      (node (ref "C55") (pin "2") (pinfunction "2_2") (pintype "passive"))
      (node (ref "C56") (pin "2") (pinfunction "2_2") (pintype "passive"))
      (node (ref "C57") (pin "1") (pinfunction "1_1") (pintype "passive"))
      (node (ref "C67") (pin "1") (pinfunction "1_1") (pintype "passive"))
      (node (ref "C68") (pin "1") (pinfunction "1_1") (pintype "passive"))
      (node (ref "FB2") (pin "P$1") (pinfunction "1_P$1") (pintype "passive"))
      (node (ref "IC11") (pin "6") (pinfunction "VCC_6") (pintype "passive"))
      (node (ref "IC12") (pin "1") (pinfunction "VDD/REF_1") (pintype "passive"))
      (node (ref "IC13") (pin "6") (pinfunction "VCC_6") (pintype "passive"))
      (node (ref "IC14") (pin "32") (pinfunction "IOVDD33-32_32") (pintype "power_in"))
      (node (ref "IC14") (pin "48") (pinfunction "IOVDD33-48_48") (pintype "power_in"))
      (node (ref "IC2") (pin "1") (pinfunction "VDD_1") (pintype "power_in"))
      (node (ref "IC4") (pin "4") (pinfunction "OUT_4") (pintype "passive"))
      (node (ref "IC5") (pin "6") (pinfunction "VCC_6") (pintype "passive"))
      (node (ref "IC6") (pin "1") (pinfunction "VDD-1_1") (pintype "power_in"))
      (node (ref "IC6") (pin "14") (pinfunction "VDD-14_14") (pintype "power_in"))
      (node (ref "IC6") (pin "27") (pinfunction "VDD-27_27") (pintype "power_in"))
      (node (ref "IC6") (pin "3") (pinfunction "VDDQ-3_3") (pintype "power_in"))
      (node (ref "IC6") (pin "43") (pinfunction "VDDQ-43_43") (pintype "power_in"))
      (node (ref "IC6") (pin "49") (pinfunction "VDDQ-49_49") (pintype "power_in"))
      (node (ref "IC6") (pin "9") (pinfunction "VDDQ-9_9") (pintype "power_in"))
      (node (ref "IC7") (pin "8") (pinfunction "VCC_8") (pintype "power_in"))
      (node (ref "J1") (pin "4") (pinfunction "VDD_4") (pintype "power_in"))
      (node (ref "JP2") (pin "2") (pinfunction "2_2") (pintype "passive"))
      (node (ref "JP5") (pin "1") (pinfunction "1_1") (pintype "passive"))
      (node (ref "JP6") (pin "NO") (pinfunction "NO_NO") (pintype "passive"))
      (node (ref "JP8") (pin "NC") (pinfunction "NC_NC") (pintype "passive"))
      (node (ref "LCD1") (pin "4") (pinfunction "VDD_4") (pintype "power_in"))
      (node (ref "R1") (pin "1") (pinfunction "1_1") (pintype "passive"))
      (node (ref "R14") (pin "1") (pinfunction "1_1") (pintype "passive"))
      (node (ref "R15") (pin "1") (pinfunction "1_1") (pintype "passive"))
      (node (ref "R16") (pin "1") (pinfunction "1_1") (pintype "passive"))
      (node (ref "R21") (pin "1") (pinfunction "1_1") (pintype "passive"))
      (node (ref "R22") (pin "1") (pinfunction "1_1") (pintype "passive"))
      (node (ref "R26") (pin "2") (pinfunction "2_2") (pintype "passive"))
      (node (ref "R30") (pin "2") (pinfunction "2_2") (pintype "passive"))
      (node (ref "R31") (pin "2") (pinfunction "2_2") (pintype "passive"))
      (node (ref "R35") (pin "1") (pinfunction "1_1") (pintype "passive"))
      (node (ref "R38") (pin "1") (pinfunction "1_1") (pintype "passive"))
      (node (ref "R39") (pin "1") (pinfunction "1_1") (pintype "passive"))
      (node (ref "R40") (pin "1") (pinfunction "1_1") (pintype "passive"))
      (node (ref "R42") (pin "1") (pinfunction "1_1") (pintype "passive"))
      (node (ref "R45") (pin "1") (pinfunction "1_1") (pintype "passive"))
      (node (ref "R46") (pin "1") (pinfunction "1_1") (pintype "passive"))
      (node (ref "R48") (pin "1") (pinfunction "1_1") (pintype "passive"))
      (node (ref "R6") (pin "1") (pinfunction "1_1") (pintype "passive"))
      (node (ref "SW3") (pin "2.1") (pinfunction "2_2.1") (pintype "passive"))
      (node (ref "SW3") (pin "2.2") (pinfunction "2_2.2") (pintype "passive"))
      (node (ref "VBUS") (pin "A") (pinfunction "A_A") (pintype "passive"))
      (node (ref "X1") (pin "7") (pinfunction "1_7") (pintype "passive"))
      (node (ref "X2") (pin "16") (pinfunction "1_16") (pintype "passive"))
      (node (ref "X5") (pin "12") (pinfunction "YELLOW_A_12") (pintype "passive"))
      (node (ref "X5") (pin "9") (pinfunction "GREEN-A_9") (pintype "passive"))
    )
    (net (code "2") (name "+3V3(A)") (class "Default")
      (node (ref "C59") (pin "2") (pinfunction "2_2") (pintype "passive"))
      (node (ref "C61") (pin "2") (pinfunction "2_2") (pintype "passive"))
      (node (ref "C66") (pin "1") (pinfunction "1_1") (pintype "passive"))
      (node (ref "FB2") (pin "P$2") (pinfunction "2_P$2") (pintype "passive"))
      (node (ref "IC14") (pin "22") (pinfunction "AVDD33_22") (pintype "power_in"))
      (node (ref "X5") (pin "3") (pinfunction "CT_3") (pintype "input"))
      (node (ref "X5") (pin "6") (pinfunction "CR_6") (pintype "input"))
    )
    (net (code "3") (name "+5V") (class "Default")
      (node (ref "C13") (pin "1") (pinfunction "+_1") (pintype "passive"))
      (node (ref "C14") (pin "1") (pinfunction "1_1") (pintype "passive"))
      (node (ref "C2") (pin "1") (pinfunction "1_1") (pintype "passive"))
      (node (ref "C47") (pin "1") (pinfunction "1_1") (pintype "passive"))
      (node (ref "D1") (pin "C") (pinfunction "C_C") (pintype "passive"))
      (node (ref "IC1") (pin "6") (pinfunction "VCC_6") (pintype "passive"))
      (node (ref "IC4") (pin "3") (pinfunction "IN_3") (pintype "input"))
      (node (ref "IC8") (pin "5") (pinfunction "IN_5") (pintype "input"))
      (node (ref "JP8") (pin "NO") (pinfunction "NO_NO") (pintype "passive"))
      (node (ref "L1") (pin "1") (pinfunction "1_1") (pintype "passive"))
      (node (ref "R23") (pin "1") (pinfunction "1_1") (pintype "passive"))
      (node (ref "X1") (pin "35") (pinfunction "1_35") (pintype "passive"))
      (node (ref "X1") (pin "36") (pinfunction "1_36") (pintype "passive"))
      (node (ref "X2") (pin "5") (pinfunction "1_5") (pintype "passive"))
      (node (ref "X2") (pin "6") (pinfunction "1_6") (pintype "passive"))
    )
    (net (code "4") (name "+12V") (class "Default")
      (node (ref "X1") (pin "37") (pinfunction "1_37") (pintype "passive"))
      (node (ref "X1") (pin "38") (pinfunction "1_38") (pintype "passive"))
      (node (ref "X2") (pin "3") (pinfunction "1_3") (pintype "passive"))
      (node (ref "X2") (pin "4") (pinfunction "1_4") (pintype "passive"))
    )
    (net (code "5") (name "+VAUX") (class "Default")
      (node (ref "JP3") (pin "2") (pinfunction "2_2") (pintype "passive"))
      (node (ref "X1") (pin "5") (pinfunction "1_5") (pintype "passive"))
      (node (ref "X2") (pin "10") (pinfunction "1_10") (pintype "passive"))
    )
    (net (code "12") (name "BOOT0") (class "Default")
      (node (ref "BOOT1") (pin "1") (pinfunction "1_1") (pintype "passive"))
      (node (ref "IC3") (pin "166") (pinfunction "BOOT0_166") (pintype "input"))
      (node (ref "R13") (pin "2") (pinfunction "2_2") (pintype "passive"))
      (node (ref "SW3") (pin "1.1") (pinfunction "1_1.1") (pintype "passive"))
      (node (ref "SW3") (pin "1.2") (pinfunction "1_1.2") (pintype "passive"))
    )
    (net (code "13") (name "BYPASS_REG") (class "Default")
      (node (ref "IC3") (pin "48") (pinfunction "BYPASS_REG_48") (pintype "input"))
      (node (ref "R12") (pin "2") (pinfunction "2_2") (pintype "passive"))
    )
    (net (code "14") (name "DAC_OUT1") (class "Default")
      (node (ref "IC3") (pin "50") (pinfunction "PA4_50") (pintype "bidirectional"))
      (node (ref "Q2") (pin "1") (pinfunction "G_1") (pintype "passive"))
    )
    (net (code "15") (name "DIN2") (class "Default")
      (node (ref "IC3") (pin "8") (pinfunction "PC13_8") (pintype "bidirectional"))
      (node (ref "R9") (pin "2") (pinfunction "2_2") (pintype "passive"))
    )
    (net (code "16") (name "DOUT2") (class "Default")
      (node (ref "IC2") (pin "7") (pinfunction "I_7") (pintype "input"))
      (node (ref "IC2") (pin "9") (pinfunction "I_9") (pintype "input"))
      (node (ref "IC3") (pin "163") (pinfunction "PB5_163") (pintype "bidirectional"))
    )
    (net (code "17") (name "ENC_A") (class "Default")
      (node (ref "C6") (pin "2") (pinfunction "2_2") (pintype "passive"))
      (node (ref "IC3") (pin "119") (pinfunction "PC6_119") (pintype "bidirectional"))
      (node (ref "R2") (pin "1") (pinfunction "1_1") (pintype "passive"))
    )
    (net (code "18") (name "ENC_B") (class "Default")
      (node (ref "C7") (pin "1") (pinfunction "1_1") (pintype "passive"))
      (node (ref "IC3") (pin "120") (pinfunction "PC7_120") (pintype "bidirectional"))
      (node (ref "R10") (pin "1") (pinfunction "1_1") (pintype "passive"))
    )
    (net (code "19") (name "ENC_SW") (class "Default")
      (node (ref "C3") (pin "2") (pinfunction "2_2") (pintype "passive"))
      (node (ref "IC3") (pin "173") (pinfunction "PI4_173") (pintype "bidirectional"))
      (node (ref "SW2") (pin "E") (pinfunction "2_E") (pintype "passive"))
    )
    (net (code "20") (name "ETH_COL") (class "Default")
      (node (ref "IC3") (pin "47") (pinfunction "PA3_47") (pintype "bidirectional"))
      (node (ref "RN2") (pin "2") (pinfunction "1_2") (pintype "passive"))
    )
    (net (code "21") (name "ETH_CRS") (class "Default")
      (node (ref "IC3") (pin "40") (pinfunction "PA0_40") (pintype "bidirectional"))
      (node (ref "JP9") (pin "1") (pinfunction "1_1") (pintype "passive"))
      (node (ref "RN1") (pin "4") (pinfunction "1_4") (pintype "passive"))
    )
    (net (code "22") (name "ETH_MDC") (class "Default")
      (node (ref "IC14") (pin "31") (pinfunction "MDC_31") (pintype "input"))
      (node (ref "IC3") (pin "33") (pinfunction "PC1_33") (pintype "bidirectional"))
    )
    (net (code "23") (name "ETH_MDIO") (class "Default")
      (node (ref "IC14") (pin "30") (pinfunction "MDIO_30") (pintype "bidirectional"))
      (node (ref "IC3") (pin "42") (pinfunction "PA2_42") (pintype "bidirectional"))
      (node (ref "R31") (pin "1") (pinfunction "1_1") (pintype "passive"))
    )
    (net (code "24") (name "ETH_RXD0") (class "Default")
      (node (ref "IC3") (pin "54") (pinfunction "PC4_54") (pintype "bidirectional"))
      (node (ref "RN2") (pin "3") (pinfunction "1_3") (pintype "passive"))
    )
    (net (code "25") (name "ETH_RXD1") (class "Default")
      (node (ref "IC3") (pin "55") (pinfunction "PC5_55") (pintype "bidirectional"))
      (node (ref "RN2") (pin "4") (pinfunction "1_4") (pintype "passive"))
    )
    (net (code "26") (name "ETH_RXD2") (class "Default")
      (node (ref "IC3") (pin "83") (pinfunction "PH6_83") (pintype "bidirectional"))
      (node (ref "RN3") (pin "1") (pinfunction "1_1") (pintype "passive"))
    )
    (net (code "27") (name "ETH_RXD3") (class "Default")
      (node (ref "IC3") (pin "84") (pinfunction "PH7_84") (pintype "bidirectional"))
      (node (ref "RN3") (pin "2") (pinfunction "1_2") (pintype "passive"))
    )
    (net (code "28") (name "ETH_RX_CLK") (class "Default")
      (node (ref "IC3") (pin "41") (pinfunction "PA1_41") (pintype "bidirectional"))
      (node (ref "RN1") (pin "2") (pinfunction "1_2") (pintype "passive"))
    )
    (net (code "29") (name "ETH_RX_DV") (class "Default")
      (node (ref "IC3") (pin "53") (pinfunction "PA7_53") (pintype "bidirectional"))
      (node (ref "RN1") (pin "3") (pinfunction "1_3") (pintype "passive"))
    )
    (net (code "30") (name "ETH_RX_ERR") (class "Default")
      (node (ref "IC3") (pin "79") (pinfunction "PB10_79") (pintype "bidirectional"))
      (node (ref "JP12") (pin "2") (pinfunction "2_2") (pintype "passive"))
    )
    (net (code "31") (name "ETH_TXD0") (class "Default")
      (node (ref "IC3") (pin "85") (pinfunction "PB12_85") (pintype "bidirectional"))
      (node (ref "RN4") (pin "1") (pinfunction "1_1") (pintype "passive"))
    )
    (net (code "32") (name "ETH_TXD1") (class "Default")
      (node (ref "IC3") (pin "86") (pinfunction "PB13_86") (pintype "bidirectional"))
      (node (ref "RN4") (pin "2") (pinfunction "1_2") (pintype "passive"))
    )
    (net (code "33") (name "ETH_TXD2") (class "Default")
      (node (ref "IC3") (pin "34") (pinfunction "PC2_34") (pintype "bidirectional"))
      (node (ref "RN4") (pin "3") (pinfunction "1_3") (pintype "passive"))
    )
    (net (code "34") (name "ETH_TXD3") (class "Default")
      (node (ref "IC3") (pin "167") (pinfunction "PB8_167") (pintype "bidirectional"))
      (node (ref "RN4") (pin "4") (pinfunction "1_4") (pintype "passive"))
    )
    (net (code "35") (name "ETH_TX_CLK") (class "Default")
      (node (ref "IC3") (pin "35") (pinfunction "PC3_35") (pintype "bidirectional"))
      (node (ref "RN3") (pin "3") (pinfunction "1_3") (pintype "passive"))
    )
    (net (code "36") (name "ETH_TX_EN") (class "Default")
      (node (ref "IC3") (pin "80") (pinfunction "PB11_80") (pintype "bidirectional"))
      (node (ref "RN3") (pin "4") (pinfunction "1_4") (pintype "passive"))
    )
    (net (code "37") (name "FMC_A0") (class "Default")
      (node (ref "IC3") (pin "16") (pinfunction "PF0_16") (pintype "bidirectional"))
      (node (ref "IC6") (pin "23") (pinfunction "A0_23") (pintype "input"))
    )
    (net (code "38") (name "FMC_A1") (class "Default")
      (node (ref "IC3") (pin "17") (pinfunction "PF1_17") (pintype "bidirectional"))
      (node (ref "IC6") (pin "24") (pinfunction "A1_24") (pintype "input"))
    )
    (net (code "39") (name "FMC_A2") (class "Default")
      (node (ref "IC3") (pin "18") (pinfunction "PF2_18") (pintype "bidirectional"))
      (node (ref "IC6") (pin "25") (pinfunction "A2_25") (pintype "input"))
    )
    (net (code "40") (name "FMC_A3") (class "Default")
      (node (ref "IC3") (pin "19") (pinfunction "PF3_19") (pintype "bidirectional"))
      (node (ref "IC6") (pin "26") (pinfunction "A3_26") (pintype "input"))
    )
    (net (code "41") (name "FMC_A4") (class "Default")
      (node (ref "IC3") (pin "20") (pinfunction "PF4_20") (pintype "bidirectional"))
      (node (ref "IC6") (pin "29") (pinfunction "A4_29") (pintype "input"))
    )
    (net (code "42") (name "FMC_A5") (class "Default")
      (node (ref "IC3") (pin "21") (pinfunction "PF5_21") (pintype "bidirectional"))
      (node (ref "IC6") (pin "30") (pinfunction "A5_30") (pintype "input"))
    )
    (net (code "43") (name "FMC_A6") (class "Default")
      (node (ref "IC3") (pin "60") (pinfunction "PF12_60") (pintype "bidirectional"))
      (node (ref "IC6") (pin "31") (pinfunction "A6_31") (pintype "input"))
    )
    (net (code "44") (name "FMC_A7") (class "Default")
      (node (ref "IC3") (pin "63") (pinfunction "PF13_63") (pintype "bidirectional"))
      (node (ref "IC6") (pin "32") (pinfunction "A7_32") (pintype "input"))
    )
    (net (code "45") (name "FMC_A8") (class "Default")
      (node (ref "IC3") (pin "64") (pinfunction "PF14_64") (pintype "bidirectional"))
      (node (ref "IC6") (pin "33") (pinfunction "A8_33") (pintype "input"))
    )
    (net (code "46") (name "FMC_A9") (class "Default")
      (node (ref "IC3") (pin "65") (pinfunction "PF15_65") (pintype "bidirectional"))
      (node (ref "IC6") (pin "34") (pinfunction "A9_34") (pintype "input"))
    )
    (net (code "47") (name "FMC_A10") (class "Default")
      (node (ref "IC3") (pin "66") (pinfunction "PG0_66") (pintype "bidirectional"))
      (node (ref "IC6") (pin "22") (pinfunction "A10/AP_22") (pintype "input"))
    )
    (net (code "48") (name "FMC_A11") (class "Default")
      (node (ref "IC3") (pin "67") (pinfunction "PG1_67") (pintype "bidirectional"))
      (node (ref "IC6") (pin "35") (pinfunction "A11_35") (pintype "input"))
    )
    (net (code "49") (name "FMC_BA0") (class "Default")
      (node (ref "IC3") (pin "112") (pinfunction "PG4_112") (pintype "bidirectional"))
      (node (ref "IC6") (pin "20") (pinfunction "BA0_20") (pintype "input"))
    )
    (net (code "50") (name "FMC_BA1") (class "Default")
      (node (ref "IC3") (pin "113") (pinfunction "PG5_113") (pintype "bidirectional"))
      (node (ref "IC6") (pin "21") (pinfunction "BA1_21") (pintype "input"))
    )
    (net (code "51") (name "FMC_D0") (class "Default")
      (node (ref "IC3") (pin "97") (pinfunction "PD14_97") (pintype "bidirectional"))
      (node (ref "IC6") (pin "2") (pinfunction "DQ0_2") (pintype "bidirectional"))
    )
    (net (code "52") (name "FMC_D1") (class "Default")
      (node (ref "IC3") (pin "98") (pinfunction "PD15_98") (pintype "bidirectional"))
      (node (ref "IC6") (pin "4") (pinfunction "DQ1_4") (pintype "bidirectional"))
    )
    (net (code "53") (name "FMC_D2") (class "Default")
      (node (ref "IC3") (pin "142") (pinfunction "PD0_142") (pintype "bidirectional"))
      (node (ref "IC6") (pin "5") (pinfunction "DQ2_5") (pintype "bidirectional"))
    )
    (net (code "54") (name "FMC_D3") (class "Default")
      (node (ref "IC3") (pin "143") (pinfunction "PD1_143") (pintype "bidirectional"))
      (node (ref "IC6") (pin "7") (pinfunction "DQ3_7") (pintype "bidirectional"))
    )
    (net (code "55") (name "FMC_D4") (class "Default")
      (node (ref "IC3") (pin "68") (pinfunction "PE7_68") (pintype "bidirectional"))
      (node (ref "IC6") (pin "8") (pinfunction "DQ4_8") (pintype "bidirectional"))
    )
    (net (code "56") (name "FMC_D5") (class "Default")
      (node (ref "IC3") (pin "69") (pinfunction "PE8_69") (pintype "bidirectional"))
      (node (ref "IC6") (pin "10") (pinfunction "DQ5_10") (pintype "bidirectional"))
    )
    (net (code "57") (name "FMC_D6") (class "Default")
      (node (ref "IC3") (pin "70") (pinfunction "PE9_70") (pintype "bidirectional"))
      (node (ref "IC6") (pin "11") (pinfunction "DQ6_11") (pintype "bidirectional"))
    )
    (net (code "58") (name "FMC_D7") (class "Default")
      (node (ref "IC3") (pin "73") (pinfunction "PE10_73") (pintype "bidirectional"))
      (node (ref "IC6") (pin "13") (pinfunction "DQ7_13") (pintype "bidirectional"))
    )
    (net (code "59") (name "FMC_D8") (class "Default")
      (node (ref "IC3") (pin "74") (pinfunction "PE11_74") (pintype "bidirectional"))
      (node (ref "IC6") (pin "42") (pinfunction "DQ8_42") (pintype "bidirectional"))
    )
    (net (code "60") (name "FMC_D9") (class "Default")
      (node (ref "IC3") (pin "75") (pinfunction "PE12_75") (pintype "bidirectional"))
      (node (ref "IC6") (pin "44") (pinfunction "DQ9_44") (pintype "bidirectional"))
    )
    (net (code "61") (name "FMC_D10") (class "Default")
      (node (ref "IC3") (pin "76") (pinfunction "PE13_76") (pintype "bidirectional"))
      (node (ref "IC6") (pin "45") (pinfunction "DQ10_45") (pintype "bidirectional"))
    )
    (net (code "62") (name "FMC_D11") (class "Default")
      (node (ref "IC3") (pin "77") (pinfunction "PE14_77") (pintype "bidirectional"))
      (node (ref "IC6") (pin "47") (pinfunction "DQ11_47") (pintype "bidirectional"))
    )
    (net (code "63") (name "FMC_D12") (class "Default")
      (node (ref "IC3") (pin "78") (pinfunction "PE15_78") (pintype "bidirectional"))
      (node (ref "IC6") (pin "48") (pinfunction "DQ12_48") (pintype "bidirectional"))
    )
    (net (code "64") (name "FMC_D13") (class "Default")
      (node (ref "IC3") (pin "89") (pinfunction "PD8_89") (pintype "bidirectional"))
      (node (ref "IC6") (pin "50") (pinfunction "DQ13_50") (pintype "bidirectional"))
    )
    (net (code "65") (name "FMC_D14") (class "Default")
      (node (ref "IC3") (pin "90") (pinfunction "PD9_90") (pintype "bidirectional"))
      (node (ref "IC6") (pin "51") (pinfunction "DQ14_51") (pintype "bidirectional"))
    )
    (net (code "66") (name "FMC_D15") (class "Default")
      (node (ref "IC3") (pin "91") (pinfunction "PD10_91") (pintype "bidirectional"))
      (node (ref "IC6") (pin "53") (pinfunction "DQ15_53") (pintype "bidirectional"))
    )
    (net (code "67") (name "FMC_NBL0") (class "Default")
      (node (ref "IC3") (pin "169") (pinfunction "PE0_169") (pintype "bidirectional"))
      (node (ref "IC6") (pin "15") (pinfunction "LDQM_15") (pintype "input"))
    )
    (net (code "68") (name "FMC_NBL1") (class "Default")
      (node (ref "IC3") (pin "170") (pinfunction "PE1_170") (pintype "bidirectional"))
      (node (ref "IC6") (pin "39") (pinfunction "UDQM_39") (pintype "input"))
    )
    (net (code "69") (name "FMC_SDCKE0") (class "Default")
      (node (ref "IC3") (pin "43") (pinfunction "PH2_43") (pintype "bidirectional"))
      (node (ref "IC6") (pin "37") (pinfunction "CKE_37") (pintype "input"))
    )
    (net (code "70") (name "FMC_SDCLK") (class "Default")
      (node (ref "IC3") (pin "116") (pinfunction "PG8_116") (pintype "bidirectional"))
      (node (ref "IC6") (pin "38") (pinfunction "CLK_38") (pintype "input"))
    )
    (net (code "71") (name "FMC_SDNCAS") (class "Default")
      (node (ref "IC3") (pin "160") (pinfunction "PG15_160") (pintype "bidirectional"))
      (node (ref "IC6") (pin "17") (pinfunction "~{CAS}_17") (pintype "input"))
    )
    (net (code "72") (name "FMC_SDNE0") (class "Default")
      (node (ref "IC3") (pin "44") (pinfunction "PH3_44") (pintype "bidirectional"))
      (node (ref "IC6") (pin "19") (pinfunction "~{CS}_19") (pintype "input"))
    )
    (net (code "73") (name "FMC_SDNRAS") (class "Default")
      (node (ref "IC3") (pin "59") (pinfunction "PF11_59") (pintype "bidirectional"))
      (node (ref "IC6") (pin "18") (pinfunction "~{RAS}_18") (pintype "input"))
    )
    (net (code "74") (name "FMC_SDNWE") (class "Default")
      (node (ref "IC3") (pin "46") (pinfunction "PH5_46") (pintype "bidirectional"))
      (node (ref "IC6") (pin "16") (pinfunction "~{WE}_16") (pintype "input"))
    )
    (net (code "75") (name "GND") (class "Default")
      (node (ref "B1") (pin "2") (pinfunction "-_2") (pintype "passive"))
      (node (ref "C1") (pin "2") (pinfunction "2_2") (pintype "passive"))
      (node (ref "C10") (pin "2") (pinfunction "2_2") (pintype "passive"))
      (node (ref "C11") (pin "1") (pinfunction "1_1") (pintype "passive"))
      (node (ref "C12") (pin "2") (pinfunction "2_2") (pintype "passive"))
      (node (ref "C13") (pin "2") (pinfunction "-_2") (pintype "passive"))
      (node (ref "C14") (pin "2") (pinfunction "2_2") (pintype "passive"))
      (node (ref "C15") (pin "-") (pinfunction "-_-") (pintype "passive"))
      (node (ref "C16") (pin "2") (pinfunction "2_2") (pintype "passive"))
      (node (ref "C17") (pin "2") (pinfunction "2_2") (pintype "passive"))
      (node (ref "C18") (pin "2") (pinfunction "2_2") (pintype "passive"))
      (node (ref "C19") (pin "2") (pinfunction "2_2") (pintype "passive"))
      (node (ref "C2") (pin "2") (pinfunction "2_2") (pintype "passive"))
      (node (ref "C20") (pin "2") (pinfunction "2_2") (pintype "passive"))
      (node (ref "C21") (pin "2") (pinfunction "2_2") (pintype "passive"))
      (node (ref "C22") (pin "-") (pinfunction "-_-") (pintype "passive"))
      (node (ref "C23") (pin "2") (pinfunction "2_2") (pintype "passive"))
      (node (ref "C24") (pin "2") (pinfunction "2_2") (pintype "passive"))
      (node (ref "C25") (pin "2") (pinfunction "2_2") (pintype "passive"))
      (node (ref "C26") (pin "2") (pinfunction "2_2") (pintype "passive"))
      (node (ref "C27") (pin "2") (pinfunction "2_2") (pintype "passive"))
      (node (ref "C28") (pin "2") (pinfunction "2_2") (pintype "passive"))
      (node (ref "C29") (pin "2") (pinfunction "2_2") (pintype "passive"))
      (node (ref "C3") (pin "1") (pinfunction "1_1") (pintype "passive"))
      (node (ref "C30") (pin "2") (pinfunction "2_2") (pintype "passive"))
      (node (ref "C31") (pin "2") (pinfunction "2_2") (pintype "passive"))
      (node (ref "C32") (pin "2") (pinfunction "2_2") (pintype "passive"))
      (node (ref "C33") (pin "2") (pinfunction "2_2") (pintype "passive"))
      (node (ref "C34") (pin "2") (pinfunction "2_2") (pintype "passive"))
      (node (ref "C35") (pin "2") (pinfunction "2_2") (pintype "passive"))
      (node (ref "C36") (pin "2") (pinfunction "2_2") (pintype "passive"))
      (node (ref "C37") (pin "2") (pinfunction "2_2") (pintype "passive"))
      (node (ref "C38") (pin "2") (pinfunction "2_2") (pintype "passive"))
      (node (ref "C39") (pin "2") (pinfunction "2_2") (pintype "passive"))
      (node (ref "C4") (pin "1") (pinfunction "1_1") (pintype "passive"))
      (node (ref "C40") (pin "1") (pinfunction "1_1") (pintype "passive"))
      (node (ref "C41") (pin "2") (pinfunction "2_2") (pintype "passive"))
      (node (ref "C42") (pin "2") (pinfunction "2_2") (pintype "passive"))
      (node (ref "C43") (pin "2") (pinfunction "2_2") (pintype "passive"))
      (node (ref "C44") (pin "2") (pinfunction "2_2") (pintype "passive"))
      (node (ref "C45") (pin "2") (pinfunction "2_2") (pintype "passive"))
      (node (ref "C46") (pin "2") (pinfunction "2_2") (pintype "passive"))
      (node (ref "C47") (pin "2") (pinfunction "2_2") (pintype "passive"))
      (node (ref "C48") (pin "2") (pinfunction "2_2") (pintype "passive"))
      (node (ref "C49") (pin "-") (pinfunction "-_-") (pintype "passive"))
      (node (ref "C5") (pin "2") (pinfunction "2_2") (pintype "passive"))
      (node (ref "C50") (pin "2") (pinfunction "2_2") (pintype "passive"))
      (node (ref "C51") (pin "2") (pinfunction "2_2") (pintype "passive"))
      (node (ref "C52") (pin "1") (pinfunction "1_1") (pintype "passive"))
      (node (ref "C53") (pin "1") (pinfunction "1_1") (pintype "passive"))
      (node (ref "C54") (pin "1") (pinfunction "1_1") (pintype "passive"))
      (node (ref "C55") (pin "1") (pinfunction "1_1") (pintype "passive"))
      (node (ref "C56") (pin "1") (pinfunction "1_1") (pintype "passive"))
      (node (ref "C57") (pin "2") (pinfunction "2_2") (pintype "passive"))
      (node (ref "C58") (pin "2") (pinfunction "2_2") (pintype "passive"))
      (node (ref "C59") (pin "1") (pinfunction "1_1") (pintype "passive"))
      (node (ref "C6") (pin "1") (pinfunction "1_1") (pintype "passive"))
      (node (ref "C60") (pin "2") (pinfunction "2_2") (pintype "passive"))
      (node (ref "C61") (pin "1") (pinfunction "1_1") (pintype "passive"))
      (node (ref "C62") (pin "2") (pinfunction "2_2") (pintype "passive"))
      (node (ref "C63") (pin "2") (pinfunction "2_2") (pintype "passive"))
      (node (ref "C64") (pin "-") (pinfunction "-_-") (pintype "passive"))
      (node (ref "C65") (pin "2") (pinfunction "2_2") (pintype "passive"))
      (node (ref "C66") (pin "2") (pinfunction "2_2") (pintype "passive"))
      (node (ref "C67") (pin "2") (pinfunction "2_2") (pintype "passive"))
      (node (ref "C68") (pin "2") (pinfunction "2_2") (pintype "passive"))
      (node (ref "C7") (pin "2") (pinfunction "2_2") (pintype "passive"))
      (node (ref "C9") (pin "1") (pinfunction "1_1") (pintype "passive"))
      (node (ref "D1") (pin "A") (pinfunction "A_A") (pintype "passive"))
      (node (ref "IC1") (pin "3") (pinfunction "GND_3") (pintype "power_in"))
      (node (ref "IC10") (pin "3") (pinfunction "GND_3") (pintype "power_in"))
      (node (ref "IC11") (pin "3") (pinfunction "GND_3") (pintype "power_in"))
      (node (ref "IC12") (pin "13") (pinfunction "A1_13") (pintype "input"))
      (node (ref "IC12") (pin "14") (pinfunction "A0_14") (pintype "input"))
      (node (ref "IC12") (pin "6") (pinfunction "GND_6") (pintype "passive"))
      (node (ref "IC13") (pin "3") (pinfunction "GND_3") (pintype "power_in"))
      (node (ref "IC14") (pin "15") (pinfunction "AGND-15_15") (pintype "power_in"))
      (node (ref "IC14") (pin "19") (pinfunction "AGND-19_19") (pintype "power_in"))
      (node (ref "IC14") (pin "35") (pinfunction "IOGND-35_35") (pintype "power_in"))
      (node (ref "IC14") (pin "36") (pinfunction "DGND_36") (pintype "power_in"))
      (node (ref "IC14") (pin "47") (pinfunction "IOGND-47_47") (pintype "power_in"))
      (node (ref "IC2") (pin "8") (pinfunction "VSS_8") (pintype "power_in"))
      (node (ref "IC3") (pin "103") (pinfunction "VSSDSI_2_103") (pintype "power_in"))
      (node (ref "IC3") (pin "109") (pinfunction "VSSDSI_109") (pintype "power_in"))
      (node (ref "IC3") (pin "117") (pinfunction "VSS_7_117") (pintype "power_in"))
      (node (ref "IC3") (pin "130") (pinfunction "VSS_8_130") (pintype "power_in"))
      (node (ref "IC3") (pin "135") (pinfunction "VSS_9_135") (pintype "power_in"))
      (node (ref "IC3") (pin "14") (pinfunction "VSS_2_14") (pintype "power_in"))
      (node (ref "IC3") (pin "148") (pinfunction "VSS_10_148") (pintype "power_in"))
      (node (ref "IC3") (pin "158") (pinfunction "VSS_158") (pintype "power_in"))
      (node (ref "IC3") (pin "22") (pinfunction "VSS_3_22") (pintype "power_in"))
      (node (ref "IC3") (pin "37") (pinfunction "VSSA_37") (pintype "power_in"))
      (node (ref "IC3") (pin "61") (pinfunction "VSS_4_61") (pintype "power_in"))
      (node (ref "IC3") (pin "71") (pinfunction "VSS_5_71") (pintype "power_in"))
      (node (ref "IC3") (pin "95") (pinfunction "VSS_6_95") (pintype "power_in"))
      (node (ref "IC4") (pin "1") (pinfunction "ADJ_1") (pintype "input"))
      (node (ref "IC5") (pin "3") (pinfunction "GND_3") (pintype "power_in"))
      (node (ref "IC6") (pin "12") (pinfunction "GNDQ-12_12") (pintype "power_in"))
      (node (ref "IC6") (pin "28") (pinfunction "GND-28_28") (pintype "power_in"))
      (node (ref "IC6") (pin "41") (pinfunction "GND_41") (pintype "power_in"))
      (node (ref "IC6") (pin "46") (pinfunction "GNDQ-46_46") (pintype "power_in"))
      (node (ref "IC6") (pin "52") (pinfunction "GNDQ-52_52") (pintype "power_in"))
      (node (ref "IC6") (pin "54") (pinfunction "GND-54_54") (pintype "power_in"))
      (node (ref "IC6") (pin "6") (pinfunction "GNDQ-6_6") (pintype "power_in"))
      (node (ref "IC7") (pin "1") (pinfunction "A0_1") (pintype "input"))
      (node (ref "IC7") (pin "2") (pinfunction "A1_2") (pintype "input"))
      (node (ref "IC7") (pin "3") (pinfunction "A2_3") (pintype "input"))
      (node (ref "IC7") (pin "4") (pinfunction "GND_4") (pintype "passive"))
      (node (ref "IC7") (pin "7") (pinfunction "WP_7") (pintype "input"))
      (node (ref "IC8") (pin "2") (pinfunction "GND_2") (pintype "power_in"))
      (node (ref "IC9") (pin "2") (pinfunction "GND_2") (pintype "power_in"))
      (node (ref "J1") (pin "6") (pinfunction "VSS_6") (pintype "power_in"))
      (node (ref "J1") (pin "S") (pinfunction "SH_S") (pintype "passive"))
      (node (ref "J1") (pin "S1") (pinfunction "SH_S1") (pintype "passive"))
      (node (ref "J1") (pin "S2") (pinfunction "SH_S2") (pintype "passive"))
      (node (ref "J1") (pin "SW2") (pinfunction "SW2_SW2") (pintype "passive"))
      (node (ref "J2") (pin "5") (pinfunction "GND_5") (pintype "passive"))
      (node (ref "JP1") (pin "1") (pinfunction "1_1") (pintype "passive"))
      (node (ref "JP6") (pin "NC") (pinfunction "NC_NC") (pintype "passive"))
      (node (ref "JP7") (pin "NC") (pinfunction "NC_NC") (pintype "passive"))
      (node (ref "LCD1") (pin "29") (pinfunction "GND-29_29") (pintype "power_in"))
      (node (ref "LCD1") (pin "3") (pinfunction "GND-3_3") (pintype "power_in"))
      (node (ref "Q1") (pin "E") (pinfunction "E_E") (pintype "passive"))
      (node (ref "Q2") (pin "2") (pinfunction "S_2") (pintype "passive"))
      (node (ref "R12") (pin "1") (pinfunction "1_1") (pintype "passive"))
      (node (ref "R13") (pin "1") (pinfunction "1_1") (pintype "passive"))
      (node (ref "R18") (pin "1") (pinfunction "1_1") (pintype "passive"))
      (node (ref "R25") (pin "2") (pinfunction "2_2") (pintype "passive"))
      (node (ref "R34") (pin "1") (pinfunction "1_1") (pintype "passive"))
      (node (ref "R37") (pin "1") (pinfunction "1_1") (pintype "passive"))
      (node (ref "R47") (pin "1") (pinfunction "1_1") (pintype "passive"))
      (node (ref "SW1") (pin "2") (pinfunction "2_2") (pintype "passive"))
      (node (ref "SW2") (pin "C") (pinfunction "C_C") (pintype "passive"))
      (node (ref "SW2") (pin "D") (pinfunction "1_D") (pintype "passive"))
      (node (ref "SW2") (pin "GND1") (pinfunction "C_GND1") (pintype "passive"))
      (node (ref "SW2") (pin "GND2") (pinfunction "C_GND2") (pintype "passive"))
      (node (ref "TP1") (pin "1") (pinfunction "P$1_1") (pintype "bidirectional"))
      (node (ref "X1") (pin "1") (pinfunction "1_1") (pintype "passive"))
      (node (ref "X1") (pin "15") (pinfunction "1_15") (pintype "passive"))
      (node (ref "X1") (pin "16") (pinfunction "1_16") (pintype "passive"))
      (node (ref "X1") (pin "2") (pinfunction "1_2") (pintype "passive"))
      (node (ref "X1") (pin "29") (pinfunction "1_29") (pintype "passive"))
      (node (ref "X1") (pin "30") (pinfunction "1_30") (pintype "passive"))
      (node (ref "X1") (pin "34") (pinfunction "1_34") (pintype "passive"))
      (node (ref "X1") (pin "39") (pinfunction "1_39") (pintype "passive"))
      (node (ref "X1") (pin "40") (pinfunction "1_40") (pintype "passive"))
      (node (ref "X2") (pin "7") (pinfunction "1_7") (pintype "passive"))
      (node (ref "X2") (pin "8") (pinfunction "1_8") (pintype "passive"))
      (node (ref "X2") (pin "9") (pinfunction "1_9") (pintype "passive"))
      (node (ref "X3") (pin "3") (pinfunction "1_3") (pintype "passive"))
      (node (ref "X4") (pin "3") (pinfunction "S_3") (pintype "passive"))
      (node (ref "X5") (pin "4") (pinfunction "GND_4") (pintype "passive"))
      (node (ref "X5") (pin "5") (pinfunction "GND_5") (pintype "passive"))
    )
    (net (code "76") (name "I2C1_SCL") (class "Default")
      (node (ref "IC12") (pin "12") (pinfunction "SCL_12") (pintype "bidirectional"))
      (node (ref "IC3") (pin "164") (pinfunction "PB6_164") (pintype "bidirectional"))
      (node (ref "IC7") (pin "6") (pinfunction "SCL_6") (pintype "bidirectional"))
      (node (ref "R15") (pin "2") (pinfunction "2_2") (pintype "passive"))
      (node (ref "SCL") (pin "1") (pinfunction "1_1") (pintype "passive"))
      (node (ref "X1") (pin "12") (pinfunction "1_12") (pintype "passive"))
    )
    (net (code "77") (name "I2C1_SDA") (class "Default")
      (node (ref "IC12") (pin "11") (pinfunction "SDA_11") (pintype "bidirectional"))
      (node (ref "IC3") (pin "165") (pinfunction "PB7_165") (pintype "bidirectional"))
      (node (ref "IC7") (pin "5") (pinfunction "SDA_5") (pintype "bidirectional"))
      (node (ref "R16") (pin "2") (pinfunction "2_2") (pintype "passive"))
      (node (ref "SDA") (pin "2") (pinfunction "2_2") (pintype "passive"))
      (node (ref "X1") (pin "14") (pinfunction "1_14") (pintype "passive"))
    )
    (net (code "78") (name "IRQ_TOUCH") (class "Default")
      (node (ref "IC12") (pin "10") (pinfunction "~{PENIRQ}_10") (pintype "output"))
      (node (ref "IC3") (pin "151") (pinfunction "PD7_151") (pintype "bidirectional"))
    )
    (net (code "79") (name "LCD_DISP") (class "Default")
      (node (ref "LCD1") (pin "31") (pinfunction "DISP_31") (pintype "input"))
      (node (ref "R30") (pin "1") (pinfunction "1_1") (pintype "passive"))
    )
    (net (code "80") (name "LED_ACT") (class "Default")
      (node (ref "IC14") (pin "26") (pinfunction "AN_EN(LED_ACT/COL)_26") (pintype "output"))
      (node (ref "R35") (pin "2") (pinfunction "2_2") (pintype "passive"))
      (node (ref "R43") (pin "2") (pinfunction "2_2") (pintype "passive"))
    )
    (net (code "81") (name "LED_LINK") (class "Default")
      (node (ref "IC14") (pin "28") (pinfunction "AN_0(LED_LINK)_28") (pintype "output"))
      (node (ref "R42") (pin "2") (pinfunction "2_2") (pintype "passive"))
      (node (ref "R44") (pin "2") (pinfunction "2_2") (pintype "passive"))
    )
    (net (code "82") (name "LED_SPEED") (class "Default")
      (node (ref "IC14") (pin "27") (pinfunction "AN_1(LED_SPEED)_27") (pintype "output"))
      (node (ref "R40") (pin "2") (pinfunction "2_2") (pintype "passive"))
      (node (ref "SPEED") (pin "C") (pinfunction "C_C") (pintype "passive"))
    )
    (net (code "83") (name "LTDC_B3") (class "Default")
      (node (ref "IC3") (pin "154") (pinfunction "PG11_154") (pintype "bidirectional"))
      (node (ref "LCD1") (pin "24") (pinfunction "B3_24") (pintype "input"))
    )
    (net (code "84") (name "LTDC_B4") (class "Default")
      (node (ref "IC3") (pin "155") (pinfunction "PG12_155") (pintype "bidirectional"))
      (node (ref "LCD1") (pin "25") (pinfunction "B4_25") (pintype "input"))
    )
    (net (code "85") (name "LTDC_B5") (class "Default")
      (node (ref "IC3") (pin "174") (pinfunction "PI5_174") (pintype "bidirectional"))
      (node (ref "LCD1") (pin "26") (pinfunction "B5_26") (pintype "input"))
    )
    (net (code "86") (name "LTDC_B6") (class "Default")
      (node (ref "IC3") (pin "175") (pinfunction "PI6_175") (pintype "bidirectional"))
      (node (ref "LCD1") (pin "27") (pinfunction "B6_27") (pintype "input"))
    )
    (net (code "87") (name "LTDC_B7") (class "Default")
      (node (ref "IC3") (pin "176") (pinfunction "PI7_176") (pintype "bidirectional"))
      (node (ref "LCD1") (pin "28") (pinfunction "B7_28") (pintype "input"))
    )
    (net (code "88") (name "LTDC_CLK") (class "Default")
      (node (ref "IC3") (pin "115") (pinfunction "PG7_115") (pintype "bidirectional"))
      (node (ref "LCD1") (pin "30") (pinfunction "CLK_30") (pintype "input"))
    )
    (net (code "89") (name "LTDC_DE") (class "Default")
      (node (ref "IC3") (pin "28") (pinfunction "PF10_28") (pintype "bidirectional"))
      (node (ref "LCD1") (pin "34") (pinfunction "DE/NC2_34") (pintype "passive"))
    )
    (net (code "90") (name "LTDC_G2") (class "Default")
      (node (ref "IC3") (pin "52") (pinfunction "PA6_52") (pintype "bidirectional"))
      (node (ref "LCD1") (pin "15") (pinfunction "G2_15") (pintype "input"))
    )
    (net (code "91") (name "LTDC_G3") (class "Default")
      (node (ref "IC3") (pin "153") (pinfunction "PG10_153") (pintype "bidirectional"))
      (node (ref "LCD1") (pin "16") (pinfunction "G3_16") (pintype "input"))
    )
    (net (code "92") (name "LTDC_G4") (class "Default")
      (node (ref "IC3") (pin "45") (pinfunction "PH4_45") (pintype "bidirectional"))
      (node (ref "LCD1") (pin "17") (pinfunction "G4_17") (pintype "input"))
    )
    (net (code "93") (name "LTDC_G5") (class "Default")
      (node (ref "IC3") (pin "132") (pinfunction "PI0_132") (pintype "bidirectional"))
      (node (ref "LCD1") (pin "18") (pinfunction "G5_18") (pintype "input"))
    )
    (net (code "94") (name "LTDC_G6") (class "Default")
      (node (ref "IC3") (pin "13") (pinfunction "PI11_13") (pintype "bidirectional"))
      (node (ref "LCD1") (pin "19") (pinfunction "G6_19") (pintype "input"))
    )
    (net (code "95") (name "LTDC_G7") (class "Default")
      (node (ref "IC3") (pin "145") (pinfunction "PD3_145") (pintype "bidirectional"))
      (node (ref "LCD1") (pin "20") (pinfunction "G7_20") (pintype "input"))
    )
    (net (code "96") (name "LTDC_HSYNC") (class "Default")
      (node (ref "IC3") (pin "12") (pinfunction "PI10_12") (pintype "bidirectional"))
      (node (ref "LCD1") (pin "32") (pinfunction "HSYNC_32") (pintype "input"))
    )
    (net (code "97") (name "LTDC_R3") (class "Default")
      (node (ref "IC3") (pin "56") (pinfunction "PB0_56") (pintype "bidirectional"))
      (node (ref "LCD1") (pin "8") (pinfunction "R3_8") (pintype "input"))
    )
    (net (code "98") (name "LTDC_R4") (class "Default")
      (node (ref "IC3") (pin "51") (pinfunction "PA5_51") (pintype "bidirectional"))
      (node (ref "LCD1") (pin "9") (pinfunction "R4_9") (pintype "input"))
    )
    (net (code "99") (name "LTDC_R5") (class "Default")
      (node (ref "IC3") (pin "32") (pinfunction "PC0_32") (pintype "bidirectional"))
      (node (ref "LCD1") (pin "10") (pinfunction "R5_10") (pintype "input"))
    )
    (net (code "100") (name "LTDC_R6") (class "Default")
      (node (ref "IC3") (pin "57") (pinfunction "PB1_57") (pintype "bidirectional"))
      (node (ref "LCD1") (pin "11") (pinfunction "R6_11") (pintype "input"))
    )
    (net (code "101") (name "LTDC_R7") (class "Default")
      (node (ref "IC3") (pin "114") (pinfunction "PG6_114") (pintype "bidirectional"))
      (node (ref "LCD1") (pin "12") (pinfunction "R7_12") (pintype "input"))
    )
    (net (code "102") (name "LTDC_VSYNC") (class "Default")
      (node (ref "IC3") (pin "11") (pinfunction "PI9_11") (pintype "bidirectional"))
      (node (ref "LCD1") (pin "33") (pinfunction "VSYNC_33") (pintype "input"))
    )
    (net (code "103") (name "MCLK_25") (class "Default")
      (node (ref "IC3") (pin "122") (pinfunction "PC9_122") (pintype "bidirectional"))
      (node (ref "RN1") (pin "1") (pinfunction "1_1") (pintype "passive"))
    )
    (net (code "104") (name "Net-(B1-+-Pad1)") (class "Default")
      (node (ref "B1") (pin "1") (pinfunction "+_1") (pintype "passive"))
      (node (ref "B1") (pin "3") (pinfunction "+_3") (pintype "passive"))
      (node (ref "JP3") (pin "1") (pinfunction "1_1") (pintype "passive"))
      (node (ref "JP4") (pin "NC") (pinfunction "NC_NC") (pintype "passive"))
    )
    (net (code "105") (name "Net-(C53-Pad2)") (class "Default")
      (node (ref "C53") (pin "2") (pinfunction "2_2") (pintype "passive"))
      (node (ref "JP8") (pin "COM") (pinfunction "COM_COM") (pintype "passive"))
      (node (ref "SP1") (pin "+B") (pinfunction "+_+B") (pintype "passive"))
      (node (ref "SP1") (pin "+B.1") (pinfunction "+_+B.1") (pintype "passive"))
    )
    (net (code "106") (name "Net-(C58-Pad1)") (class "Default")
      (node (ref "C58") (pin "1") (pinfunction "1_1") (pintype "passive"))
      (node (ref "R32") (pin "1") (pinfunction "1_1") (pintype "passive"))
      (node (ref "R33") (pin "2") (pinfunction "2_2") (pintype "passive"))
    )
    (net (code "107") (name "Net-(C60-Pad1)") (class "Default")
      (node (ref "C60") (pin "1") (pinfunction "1_1") (pintype "passive"))
      (node (ref "R36") (pin "1") (pinfunction "1_1") (pintype "passive"))
      (node (ref "R41") (pin "2") (pinfunction "2_2") (pintype "passive"))
    )
    (net (code "108") (name "Net-(IC1-IO1)") (class "Default")
      (node (ref "IC1") (pin "1") (pinfunction "IO1_1") (pintype "bidirectional"))
      (node (ref "R3") (pin "1") (pinfunction "1_1") (pintype "passive"))
      (node (ref "X3") (pin "1") (pinfunction "1_1") (pintype "passive"))
    )
    (net (code "109") (name "Net-(IC1-IO2)") (class "Default")
      (node (ref "IC1") (pin "2") (pinfunction "IO2_2") (pintype "bidirectional"))
      (node (ref "R7") (pin "1") (pinfunction "1_1") (pintype "passive"))
      (node (ref "X3") (pin "2") (pinfunction "1_2") (pintype "passive"))
    )
    (net (code "110") (name "Net-(IC1-IO3)") (class "Default")
      (node (ref "IC1") (pin "4") (pinfunction "IO3_4") (pintype "bidirectional"))
      (node (ref "IC2") (pin "12") (pinfunction "O_12") (pintype "output"))
      (node (ref "IC2") (pin "4") (pinfunction "O_4") (pintype "output"))
      (node (ref "X3") (pin "4") (pinfunction "1_4") (pintype "passive"))
    )
    (net (code "111") (name "Net-(IC1-IO4)") (class "Default")
      (node (ref "IC1") (pin "5") (pinfunction "IO4_5") (pintype "bidirectional"))
      (node (ref "IC2") (pin "10") (pinfunction "O_10") (pintype "output"))
      (node (ref "IC2") (pin "6") (pinfunction "O_6") (pintype "output"))
      (node (ref "X3") (pin "5") (pinfunction "1_5") (pintype "passive"))
    )
    (net (code "112") (name "Net-(IC2A-I)") (class "Default")
      (node (ref "IC2") (pin "3") (pinfunction "I_3") (pintype "input"))
      (node (ref "R8") (pin "2") (pinfunction "2_2") (pintype "passive"))
    )
    (net (code "113") (name "Net-(IC2A-O)") (class "Default")
      (node (ref "IC2") (pin "2") (pinfunction "O_2") (pintype "output"))
      (node (ref "R9") (pin "1") (pinfunction "1_1") (pintype "passive"))
    )
    (net (code "114") (name "Net-(IC2F-I)") (class "Default")
      (node (ref "IC2") (pin "14") (pinfunction "I_14") (pintype "input"))
      (node (ref "R4") (pin "2") (pinfunction "2_2") (pintype "passive"))
    )
    (net (code "115") (name "Net-(IC2F-O)") (class "Default")
      (node (ref "IC2") (pin "15") (pinfunction "O_15") (pintype "output"))
      (node (ref "R5") (pin "1") (pinfunction "1_1") (pintype "passive"))
    )
    (net (code "116") (name "Net-(IC3D-VCAPDSI)") (class "Default")
      (node (ref "IC3") (pin "100") (pinfunction "VCAPDSI_100") (pintype "power_in"))
      (node (ref "IC3") (pin "106") (pinfunction "VDD12DSI_106") (pintype "power_in"))
    )
    (net (code "117") (name "Net-(IC9-SW)") (class "Default")
      (node (ref "D2") (pin "A") (pinfunction "A_A") (pintype "passive"))
      (node (ref "IC9") (pin "1") (pinfunction "SW_1") (pintype "output"))
      (node (ref "L1") (pin "2") (pinfunction "2_2") (pintype "passive"))
    )
    (net (code "118") (name "Net-(IC9-VIN)") (class "Default")
      (node (ref "IC9") (pin "5") (pinfunction "VIN_5") (pintype "input"))
      (node (ref "R23") (pin "2") (pinfunction "2_2") (pintype "passive"))
    )
    (net (code "119") (name "Net-(IC13-IO1)") (class "Default")
      (node (ref "IC13") (pin "1") (pinfunction "IO1_1") (pintype "bidirectional"))
      (node (ref "IC14") (pin "17") (pinfunction "TD+_17") (pintype "bidirectional"))
      (node (ref "R32") (pin "2") (pinfunction "2_2") (pintype "passive"))
      (node (ref "X5") (pin "1") (pinfunction "TD+_1") (pintype "input"))
    )
    (net (code "120") (name "Net-(IC13-IO2)") (class "Default")
      (node (ref "IC13") (pin "2") (pinfunction "IO2_2") (pintype "bidirectional"))
      (node (ref "IC14") (pin "16") (pinfunction "TD-_16") (pintype "bidirectional"))
      (node (ref "R33") (pin "1") (pinfunction "1_1") (pintype "passive"))
      (node (ref "X5") (pin "2") (pinfunction "TD-_2") (pintype "input"))
    )
    (net (code "121") (name "Net-(IC13-IO3)") (class "Default")
      (node (ref "IC13") (pin "4") (pinfunction "IO3_4") (pintype "bidirectional"))
      (node (ref "IC14") (pin "14") (pinfunction "RD+_14") (pintype "bidirectional"))
      (node (ref "R36") (pin "2") (pinfunction "2_2") (pintype "passive"))
      (node (ref "X5") (pin "7") (pinfunction "RD+_7") (pintype "input"))
    )
    (net (code "122") (name "Net-(IC13-IO4)") (class "Default")
      (node (ref "IC13") (pin "5") (pinfunction "IO4_5") (pintype "bidirectional"))
      (node (ref "IC14") (pin "13") (pinfunction "RD-_13") (pintype "bidirectional"))
      (node (ref "R41") (pin "1") (pinfunction "1_1") (pintype "passive"))
      (node (ref "X5") (pin "8") (pinfunction "RD-_8") (pintype "input"))
    )
    (net (code "123") (name "Net-(IC14-CRS{slash}CRS_DV{slash}LED_CFG)") (class "Default")
      (node (ref "IC14") (pin "40") (pinfunction "CRS/CRS_DV/LED_CFG_40") (pintype "output"))
      (node (ref "RN1") (pin "5") (pinfunction "2_5") (pintype "passive"))
    )
    (net (code "124") (name "Net-(IC14-MDIX_EN(RX_ER))") (class "Default")
      (node (ref "IC14") (pin "41") (pinfunction "MDIX_EN(RX_ER)_41") (pintype "output"))
      (node (ref "RN2") (pin "8") (pinfunction "2_8") (pintype "passive"))
    )
    (net (code "125") (name "Net-(IC14-MII_MODE(RX_DV))") (class "Default")
      (node (ref "IC14") (pin "39") (pinfunction "MII_MODE(RX_DV)_39") (pintype "output"))
      (node (ref "JP11") (pin "2") (pinfunction "2_2") (pintype "passive"))
      (node (ref "RN1") (pin "6") (pinfunction "2_6") (pintype "passive"))
    )
    (net (code "126") (name "Net-(IC14-PFBIN1)") (class "Default")
      (node (ref "C62") (pin "1") (pinfunction "1_1") (pintype "passive"))
      (node (ref "C63") (pin "1") (pinfunction "1_1") (pintype "passive"))
      (node (ref "C64") (pin "+") (pinfunction "+_+") (pintype "passive"))
      (node (ref "C65") (pin "1") (pinfunction "1_1") (pintype "passive"))
      (node (ref "IC14") (pin "18") (pinfunction "PFBIN1_18") (pintype "input"))
      (node (ref "IC14") (pin "23") (pinfunction "PFBOUT_23") (pintype "output"))
      (node (ref "IC14") (pin "37") (pinfunction "PFBIN2_37") (pintype "input"))
    )
    (net (code "127") (name "Net-(IC14-PHYAD0(COL))") (class "Default")
      (node (ref "IC14") (pin "42") (pinfunction "PHYAD0(COL)_42") (pintype "output"))
      (node (ref "RN2") (pin "7") (pinfunction "2_7") (pintype "passive"))
    )
    (net (code "128") (name "Net-(IC14-PHYAD1(RXD1_0))") (class "Default")
      (node (ref "IC14") (pin "43") (pinfunction "PHYAD1(RXD1_0)_43") (pintype "output"))
      (node (ref "RN2") (pin "6") (pinfunction "2_6") (pintype "passive"))
    )
    (net (code "129") (name "Net-(IC14-PHYAD2(RXD1_1))") (class "Default")
      (node (ref "IC14") (pin "44") (pinfunction "PHYAD2(RXD1_1)_44") (pintype "output"))
      (node (ref "RN2") (pin "5") (pinfunction "2_5") (pintype "passive"))
    )
    (net (code "130") (name "Net-(IC14-PHYAD3(RXD1_2))") (class "Default")
      (node (ref "IC14") (pin "45") (pinfunction "PHYAD3(RXD1_2)_45") (pintype "output"))
      (node (ref "RN3") (pin "8") (pinfunction "2_8") (pintype "passive"))
    )
    (net (code "131") (name "Net-(IC14-PHYAD4(RXD1_3))") (class "Default")
      (node (ref "IC14") (pin "46") (pinfunction "PHYAD4(RXD1_3)_46") (pintype "output"))
      (node (ref "RN3") (pin "7") (pinfunction "2_7") (pintype "passive"))
    )
    (net (code "132") (name "Net-(IC14-PWR_DOWN{slash}INT)") (class "Default")
      (node (ref "IC14") (pin "7") (pinfunction "PWR_DOWN/INT_7") (pintype "input"))
      (node (ref "JP13") (pin "2") (pinfunction "2_2") (pintype "passive"))
    )
    (net (code "133") (name "Net-(IC14-RBIAS)") (class "Default")
      (node (ref "IC14") (pin "24") (pinfunction "RBIAS_24") (pintype "input"))
      (node (ref "R47") (pin "2") (pinfunction "2_2") (pintype "passive"))
    )
    (net (code "134") (name "Net-(IC14-RESERVED-20)") (class "Default")
      (node (ref "IC14") (pin "20") (pinfunction "RESERVED-20_20") (pintype "bidirectional"))
      (node (ref "R46") (pin "2") (pinfunction "2_2") (pintype "passive"))
    )
    (net (code "135") (name "Net-(IC14-RESERVED-21)") (class "Default")
      (node (ref "IC14") (pin "21") (pinfunction "RESERVED-21_21") (pintype "bidirectional"))
      (node (ref "R45") (pin "2") (pinfunction "2_2") (pintype "passive"))
    )
    (net (code "136") (name "Net-(IC14-RX_CLK)") (class "Default")
      (node (ref "IC14") (pin "38") (pinfunction "RX_CLK_38") (pintype "output"))
      (node (ref "RN1") (pin "7") (pinfunction "2_7") (pintype "passive"))
    )
    (net (code "137") (name "Net-(IC14-TXD_0)") (class "Default")
      (node (ref "IC14") (pin "3") (pinfunction "TXD_0_3") (pintype "input"))
      (node (ref "RN4") (pin "8") (pinfunction "2_8") (pintype "passive"))
    )
    (net (code "138") (name "Net-(IC14-TXD_1)") (class "Default")
      (node (ref "IC14") (pin "4") (pinfunction "TXD_1_4") (pintype "input"))
      (node (ref "RN4") (pin "7") (pinfunction "2_7") (pintype "passive"))
    )
    (net (code "139") (name "Net-(IC14-TXD_2)") (class "Default")
      (node (ref "IC14") (pin "5") (pinfunction "TXD_2_5") (pintype "input"))
      (node (ref "RN4") (pin "6") (pinfunction "2_6") (pintype "passive"))
    )
    (net (code "140") (name "Net-(IC14-TXD_3{slash}SNI_MODE)") (class "Default")
      (node (ref "IC14") (pin "6") (pinfunction "TXD_3/SNI_MODE_6") (pintype "input"))
      (node (ref "RN4") (pin "5") (pinfunction "2_5") (pintype "passive"))
    )
    (net (code "141") (name "Net-(IC14-TX_CLK)") (class "Default")
      (node (ref "IC14") (pin "1") (pinfunction "TX_CLK_1") (pintype "output"))
      (node (ref "RN3") (pin "6") (pinfunction "2_6") (pintype "passive"))
    )
    (net (code "142") (name "Net-(IC14-TX_EN)") (class "Default")
      (node (ref "IC14") (pin "2") (pinfunction "TX_EN_2") (pintype "input"))
      (node (ref "RN3") (pin "5") (pinfunction "2_5") (pintype "passive"))
    )
    (net (code "143") (name "Net-(IC14-X1)") (class "Default")
      (node (ref "IC14") (pin "34") (pinfunction "X1_34") (pintype "input"))
      (node (ref "RN1") (pin "8") (pinfunction "2_8") (pintype "passive"))
    )
    (net (code "144") (name "Net-(JP9-Pad2)") (class "Default")
      (node (ref "JP9") (pin "2") (pinfunction "2_2") (pintype "passive"))
      (node (ref "R37") (pin "2") (pinfunction "2_2") (pintype "passive"))
    )
    (net (code "145") (name "Net-(JP10-Pad1)") (class "Default")
      (node (ref "JP10") (pin "1") (pinfunction "1_1") (pintype "passive"))
      (node (ref "JP12") (pin "1") (pinfunction "1_1") (pintype "passive"))
      (node (ref "RN2") (pin "1") (pinfunction "1_1") (pintype "passive"))
    )
    (net (code "146") (name "Net-(JP10-Pad2)") (class "Default")
      (node (ref "JP10") (pin "2") (pinfunction "2_2") (pintype "passive"))
      (node (ref "R34") (pin "2") (pinfunction "2_2") (pintype "passive"))
    )
    (net (code "147") (name "Net-(JP11-Pad1)") (class "Default")
      (node (ref "JP11") (pin "1") (pinfunction "1_1") (pintype "passive"))
      (node (ref "R39") (pin "2") (pinfunction "2_2") (pintype "passive"))
    )
    (net (code "148") (name "Net-(JP13-Pad1)") (class "Default")
      (node (ref "JP13") (pin "1") (pinfunction "1_1") (pintype "passive"))
      (node (ref "R48") (pin "2") (pinfunction "2_2") (pintype "passive"))
    )
    (net (code "149") (name "Net-(LCD1-B0)") (class "Default")
      (node (ref "JP6") (pin "COM") (pinfunction "COM_COM") (pintype "passive"))
      (node (ref "LCD1") (pin "13") (pinfunction "G0_13") (pintype "input"))
      (node (ref "LCD1") (pin "14") (pinfunction "G1_14") (pintype "input"))
      (node (ref "LCD1") (pin "21") (pinfunction "B0_21") (pintype "input"))
      (node (ref "LCD1") (pin "22") (pinfunction "B1_22") (pintype "input"))
      (node (ref "LCD1") (pin "23") (pinfunction "B2_23") (pintype "input"))
      (node (ref "LCD1") (pin "5") (pinfunction "R0_5") (pintype "input"))
      (node (ref "LCD1") (pin "6") (pinfunction "R1_6") (pintype "input"))
      (node (ref "LCD1") (pin "7") (pinfunction "R2_7") (pintype "input"))
    )
    (net (code "150") (name "Net-(LCD1-RESET)") (class "Default")
      (node (ref "JP7") (pin "COM") (pinfunction "COM_COM") (pintype "passive"))
      (node (ref "LCD1") (pin "36") (pinfunction "RESET_36") (pintype "input"))
    )
    (net (code "151") (name "Net-(Q1-PadB)") (class "Default")
      (node (ref "Q1") (pin "B") (pinfunction "B_B") (pintype "passive"))
      (node (ref "R27") (pin "2") (pinfunction "2_2") (pintype "passive"))
    )
    (net (code "152") (name "Net-(Q1-PadC)") (class "Default")
      (node (ref "Q1") (pin "C") (pinfunction "C_C") (pintype "passive"))
      (node (ref "R24") (pin "1") (pinfunction "1_1") (pintype "passive"))
    )
    (net (code "153") (name "Net-(Q2-D)") (class "Default")
      (node (ref "Q2") (pin "3") (pinfunction "D_3") (pintype "passive"))
      (node (ref "SP1") (pin "-B") (pinfunction "-_-B") (pintype "passive"))
      (node (ref "SP1") (pin "-B.1") (pinfunction "-_-B.1") (pintype "passive"))
    )
    (net (code "154") (name "Net-(R1-Pad2)") (class "Default")
      (node (ref "R1") (pin "2") (pinfunction "2_2") (pintype "passive"))
      (node (ref "R2") (pin "2") (pinfunction "2_2") (pintype "passive"))
      (node (ref "SW2") (pin "A") (pinfunction "A_A") (pintype "passive"))
    )
    (net (code "155") (name "Net-(R3-Pad2)") (class "Default")
      (node (ref "R3") (pin "2") (pinfunction "2_2") (pintype "passive"))
      (node (ref "R4") (pin "1") (pinfunction "1_1") (pintype "passive"))
    )
    (net (code "156") (name "Net-(R7-Pad2)") (class "Default")
      (node (ref "R7") (pin "2") (pinfunction "2_2") (pintype "passive"))
      (node (ref "R8") (pin "1") (pinfunction "1_1") (pintype "passive"))
    )
    (net (code "157") (name "Net-(R10-Pad2)") (class "Default")
      (node (ref "R10") (pin "2") (pinfunction "2_2") (pintype "passive"))
      (node (ref "R6") (pin "2") (pinfunction "2_2") (pintype "passive"))
      (node (ref "SW2") (pin "B") (pinfunction "B_B") (pintype "passive"))
    )
    (net (code "158") (name "Net-(R24-Pad2)") (class "Default")
      (node (ref "R24") (pin "2") (pinfunction "2_2") (pintype "passive"))
      (node (ref "VBUS") (pin "C") (pinfunction "C_C") (pintype "passive"))
    )
    (net (code "159") (name "Net-(R38-Pad2)") (class "Default")
      (node (ref "R38") (pin "2") (pinfunction "2_2") (pintype "passive"))
      (node (ref "SPEED") (pin "A") (pinfunction "A_A") (pintype "passive"))
    )
    (net (code "160") (name "Net-(X2E-1)") (class "Default")
      (node (ref "SCL") (pin "2") (pinfunction "2_2") (pintype "passive"))
      (node (ref "X2") (pin "13") (pinfunction "1_13") (pintype "passive"))
    )
    (net (code "161") (name "Net-(X2F-1)") (class "Default")
      (node (ref "SDA") (pin "1") (pinfunction "1_1") (pintype "passive"))
      (node (ref "X2") (pin "14") (pinfunction "1_14") (pintype "passive"))
    )
    (net (code "162") (name "Net-(X4A-S)") (class "Default")
      (node (ref "JP5") (pin "2") (pinfunction "2_2") (pintype "passive"))
      (node (ref "R18") (pin "2") (pinfunction "2_2") (pintype "passive"))
      (node (ref "X4") (pin "1") (pinfunction "S_1") (pintype "passive"))
    )
    (net (code "163") (name "Net-(X5-GREEN-C)") (class "Default")
      (node (ref "R44") (pin "1") (pinfunction "1_1") (pintype "passive"))
      (node (ref "X5") (pin "10") (pinfunction "GREEN-C_10") (pintype "passive"))
    )
    (net (code "164") (name "Net-(X5-YELLOW-C)") (class "Default")
      (node (ref "R43") (pin "1") (pinfunction "1_1") (pintype "passive"))
      (node (ref "X5") (pin "11") (pinfunction "YELLOW-C_11") (pintype "passive"))
    )
    (net (code "165") (name "OE_SYNC") (class "Default")
      (node (ref "IC3") (pin "94") (pinfunction "PD13_94") (pintype "bidirectional"))
      (node (ref "X1") (pin "10") (pinfunction "1_10") (pintype "passive"))
    )
    (net (code "166") (name "PE") (class "Default")
      (node (ref "C1") (pin "1") (pinfunction "1_1") (pintype "passive"))
      (node (ref "C51") (pin "1") (pinfunction "1_1") (pintype "passive"))
      (node (ref "J2") (pin "SH1") (pinfunction "SH1_SH1") (pintype "bidirectional"))
      (node (ref "J2") (pin "SH1.1") (pinfunction "SH1_SH1.1") (pintype "bidirectional"))
      (node (ref "J2") (pin "SH2") (pinfunction "SH2_SH2") (pintype "bidirectional"))
      (node (ref "J2") (pin "SH2.2") (pinfunction "SH2_SH2.2") (pintype "bidirectional"))
      (node (ref "JP1") (pin "2") (pinfunction "2_2") (pintype "passive"))
      (node (ref "X2") (pin "1") (pinfunction "1_1") (pintype "passive"))
      (node (ref "X5") (pin "SH") (pinfunction "SH_SH") (pintype "passive"))
      (node (ref "X5") (pin "SH2") (pinfunction "SH_SH2") (pintype "passive"))
    )
    (net (code "167") (name "PWR_DIRECT") (class "Default")
      (node (ref "IC3") (pin "110") (pinfunction "PG2_110") (pintype "bidirectional"))
      (node (ref "X2") (pin "12") (pinfunction "1_12") (pintype "passive"))
    )
    (net (code "168") (name "PWR_SSTART") (class "Default")
      (node (ref "IC3") (pin "111") (pinfunction "PG3_111") (pintype "bidirectional"))
      (node (ref "X2") (pin "11") (pinfunction "1_11") (pintype "passive"))
    )
    (net (code "169") (name "RCC_OSC32_IN") (class "Default")
      (node (ref "C10") (pin "1") (pinfunction "1_1") (pintype "passive"))
      (node (ref "IC3") (pin "9") (pinfunction "PC14_9") (pintype "bidirectional"))
      (node (ref "Y2") (pin "1") (pinfunction "1_1") (pintype "passive"))
    )
    (net (code "170") (name "RCC_OSC32_OUT") (class "Default")
      (node (ref "C12") (pin "1") (pinfunction "1_1") (pintype "passive"))
      (node (ref "IC3") (pin "10") (pinfunction "PC15_10") (pintype "bidirectional"))
      (node (ref "Y2") (pin "4") (pinfunction "2_4") (pintype "passive"))
    )
    (net (code "171") (name "RCC_OSC_IN") (class "Default")
      (node (ref "C9") (pin "2") (pinfunction "2_2") (pintype "passive"))
      (node (ref "IC3") (pin "29") (pinfunction "PH0_29") (pintype "bidirectional"))
      (node (ref "Y1") (pin "2") (pinfunction "2_2") (pintype "passive"))
    )
    (net (code "172") (name "RCC_OSC_OUT") (class "Default")
      (node (ref "C11") (pin "2") (pinfunction "2_2") (pintype "passive"))
      (node (ref "IC3") (pin "30") (pinfunction "PH1_30") (pintype "bidirectional"))
      (node (ref "Y1") (pin "1") (pinfunction "1_1") (pintype "passive"))
    )
    (net (code "173") (name "SDMMC1_CK") (class "Default")
      (node (ref "IC3") (pin "141") (pinfunction "PC12_141") (pintype "bidirectional"))
      (node (ref "J1") (pin "5") (pinfunction "CLK_5") (pintype "passive"))
    )
    (net (code "174") (name "SDMMC1_CMD") (class "Default")
      (node (ref "IC3") (pin "144") (pinfunction "PD2_144") (pintype "bidirectional"))
      (node (ref "J1") (pin "3") (pinfunction "CMD_3") (pintype "passive"))
      (node (ref "R22") (pin "2") (pinfunction "2_2") (pintype "passive"))
    )
    (net (code "175") (name "SDMMC1_D0") (class "Default")
      (node (ref "IC3") (pin "121") (pinfunction "PC8_121") (pintype "bidirectional"))
      (node (ref "J1") (pin "7") (pinfunction "DAT0_7") (pintype "passive"))
      (node (ref "R21") (pin "2") (pinfunction "2_2") (pintype "passive"))
    )
    (net (code "176") (name "SD_DETECT") (class "Default")
      (node (ref "IC3") (pin "140") (pinfunction "PC11_140") (pintype "bidirectional"))
      (node (ref "J1") (pin "SW1") (pinfunction "SW1_SW1") (pintype "passive"))
    )
    (net (code "177") (name "SPI2_CLK") (class "Default")
      (node (ref "IC3") (pin "133") (pinfunction "PI1_133") (pintype "bidirectional"))
      (node (ref "X1") (pin "32") (pinfunction "1_32") (pintype "passive"))
    )
    (net (code "178") (name "SPI2_CSA") (class "Default")
      (node (ref "IC3") (pin "93") (pinfunction "PD12_93") (pintype "bidirectional"))
      (node (ref "X1") (pin "28") (pinfunction "1_28") (pintype "passive"))
    )
    (net (code "179") (name "SPI2_CSB") (class "Default")
      (node (ref "IC3") (pin "92") (pinfunction "PD11_92") (pintype "bidirectional"))
      (node (ref "X1") (pin "27") (pinfunction "1_27") (pintype "passive"))
    )
    (net (code "180") (name "SPI2_IRQ") (class "Default")
      (node (ref "IC3") (pin "123") (pinfunction "PA8_123") (pintype "bidirectional"))
      (node (ref "X1") (pin "25") (pinfunction "1_25") (pintype "passive"))
    )
    (net (code "181") (name "SPI2_MISO") (class "Default")
      (node (ref "IC3") (pin "87") (pinfunction "PB14_87") (pintype "bidirectional"))
      (node (ref "X1") (pin "31") (pinfunction "1_31") (pintype "passive"))
    )
    (net (code "182") (name "SPI2_MOSI") (class "Default")
      (node (ref "IC3") (pin "134") (pinfunction "PI3_134") (pintype "bidirectional"))
      (node (ref "X1") (pin "33") (pinfunction "1_33") (pintype "passive"))
    )
    (net (code "183") (name "SPI4_CLK") (class "Default")
      (node (ref "IC3") (pin "1") (pinfunction "PE2_1") (pintype "bidirectional"))
      (node (ref "X1") (pin "23") (pinfunction "1_23") (pintype "passive"))
    )
    (net (code "184") (name "SPI4_CSA") (class "Default")
      (node (ref "IC3") (pin "2") (pinfunction "PE3_2") (pintype "bidirectional"))
      (node (ref "X1") (pin "22") (pinfunction "1_22") (pintype "passive"))
    )
    (net (code "185") (name "SPI4_CSB") (class "Default")
      (node (ref "IC3") (pin "3") (pinfunction "PE4_3") (pintype "bidirectional"))
      (node (ref "X1") (pin "21") (pinfunction "1_21") (pintype "passive"))
    )
    (net (code "186") (name "SPI4_IRQ") (class "Default")
      (node (ref "IC3") (pin "168") (pinfunction "PB9_168") (pintype "bidirectional"))
      (node (ref "X1") (pin "19") (pinfunction "1_19") (pintype "passive"))
    )
    (net (code "187") (name "SPI4_MISO") (class "Default")
      (node (ref "IC3") (pin "4") (pinfunction "PE5_4") (pintype "bidirectional"))
      (node (ref "X1") (pin "24") (pinfunction "1_24") (pintype "passive"))
    )
    (net (code "188") (name "SPI4_MOSI") (class "Default")
      (node (ref "IC3") (pin "5") (pinfunction "PE6_5") (pintype "bidirectional"))
      (node (ref "X1") (pin "26") (pinfunction "1_26") (pintype "passive"))
    )
    (net (code "189") (name "SPI5_CLK") (class "Default")
      (node (ref "IC3") (pin "25") (pinfunction "PF7_25") (pintype "bidirectional"))
      (node (ref "X1") (pin "17") (pinfunction "1_17") (pintype "passive"))
    )
    (net (code "190") (name "SPI5_CSA") (class "Default")
      (node (ref "IC3") (pin "157") (pinfunction "PG14_157") (pintype "bidirectional"))
      (node (ref "X1") (pin "11") (pinfunction "1_11") (pintype "passive"))
    )
    (net (code "191") (name "SPI5_CSB") (class "Default")
      (node (ref "IC3") (pin "156") (pinfunction "PG13_156") (pintype "bidirectional"))
      (node (ref "X1") (pin "13") (pinfunction "1_13") (pintype "passive"))
    )
    (net (code "192") (name "SPI5_IRQ") (class "Default")
      (node (ref "IC3") (pin "138") (pinfunction "PA15_138") (pintype "bidirectional"))
      (node (ref "X1") (pin "9") (pinfunction "1_9") (pintype "passive"))
    )
    (net (code "193") (name "SPI5_MISO") (class "Default")
      (node (ref "IC3") (pin "26") (pinfunction "PF8_26") (pintype "bidirectional"))
      (node (ref "X1") (pin "18") (pinfunction "1_18") (pintype "passive"))
    )
    (net (code "194") (name "SPI5_MOSI") (class "Default")
      (node (ref "IC3") (pin "27") (pinfunction "PF9_27") (pintype "bidirectional"))
      (node (ref "X1") (pin "20") (pinfunction "1_20") (pintype "passive"))
    )
    (net (code "195") (name "SYS_JTCK-SWCLK") (class "Default")
      (node (ref "IC3") (pin "137") (pinfunction "PA14_137") (pintype "bidirectional"))
      (node (ref "R20") (pin "1") (pinfunction "1_1") (pintype "passive"))
    )
    (net (code "196") (name "SYS_JTDO-SWO") (class "Default")
      (node (ref "IC3") (pin "161") (pinfunction "PB3_161") (pintype "bidirectional"))
      (node (ref "IC5") (pin "5") (pinfunction "IO4_5") (pintype "bidirectional"))
      (node (ref "X4") (pin "6") (pinfunction "S_6") (pintype "passive"))
    )
    (net (code "197") (name "SYS_JTMS-SWDIO") (class "Default")
      (node (ref "IC3") (pin "128") (pinfunction "PA13_128") (pintype "bidirectional"))
      (node (ref "R19") (pin "1") (pinfunction "1_1") (pintype "passive"))
    )
    (net (code "198") (name "TCK") (class "Default")
      (node (ref "IC5") (pin "1") (pinfunction "IO1_1") (pintype "bidirectional"))
      (node (ref "R20") (pin "2") (pinfunction "2_2") (pintype "passive"))
      (node (ref "X4") (pin "2") (pinfunction "S_2") (pintype "passive"))
    )
    (net (code "199") (name "TFT_BRIGHTNESS") (class "Default")
      (node (ref "IC3") (pin "88") (pinfunction "PB15_88") (pintype "bidirectional"))
      (node (ref "IC9") (pin "4") (pinfunction "CTRL_4") (pintype "input"))
    )
    (net (code "200") (name "TMS") (class "Default")
      (node (ref "IC5") (pin "2") (pinfunction "IO2_2") (pintype "bidirectional"))
      (node (ref "R19") (pin "2") (pinfunction "2_2") (pintype "passive"))
      (node (ref "X4") (pin "4") (pinfunction "S_4") (pintype "passive"))
    )
    (net (code "201") (name "UART_RX{slash}DIN1") (class "Default")
      (node (ref "IC3") (pin "24") (pinfunction "PF6_24") (pintype "bidirectional"))
      (node (ref "R5") (pin "2") (pinfunction "2_2") (pintype "passive"))
      (node (ref "X1") (pin "3") (pinfunction "1_3") (pintype "passive"))
    )
    (net (code "202") (name "UART_TX{slash}DOUT1") (class "Default")
      (node (ref "IC2") (pin "11") (pinfunction "I_11") (pintype "input"))
      (node (ref "IC2") (pin "5") (pinfunction "I_5") (pintype "input"))
      (node (ref "IC3") (pin "162") (pinfunction "PB4_162") (pintype "bidirectional"))
      (node (ref "X1") (pin "4") (pinfunction "1_4") (pintype "passive"))
    )
    (net (code "203") (name "USB_D_N") (class "Default")
      (node (ref "IC10") (pin "1") (pinfunction "IO1_1") (pintype "bidirectional"))
      (node (ref "J2") (pin "2") (pinfunction "D-_2") (pintype "passive"))
      (node (ref "R28") (pin "1") (pinfunction "1_1") (pintype "passive"))
    )
    (net (code "204") (name "USB_D_P") (class "Default")
      (node (ref "IC10") (pin "2") (pinfunction "IO2_2") (pintype "bidirectional"))
      (node (ref "J2") (pin "3") (pinfunction "D+_3") (pintype "passive"))
      (node (ref "R29") (pin "1") (pinfunction "1_1") (pintype "passive"))
    )
    (net (code "205") (name "USB_OTG_FS_D_N") (class "Default")
      (node (ref "IC3") (pin "126") (pinfunction "PA11_126") (pintype "bidirectional"))
      (node (ref "R28") (pin "2") (pinfunction "2_2") (pintype "passive"))
    )
    (net (code "206") (name "USB_OTG_FS_D_P") (class "Default")
      (node (ref "IC3") (pin "127") (pinfunction "PA12_127") (pintype "bidirectional"))
      (node (ref "R29") (pin "2") (pinfunction "2_2") (pintype "passive"))
    )
    (net (code "207") (name "USB_OTG_FS_ID") (class "Default")
      (node (ref "IC10") (pin "4") (pinfunction "IO3_4") (pintype "bidirectional"))
      (node (ref "IC3") (pin "125") (pinfunction "PA10_125") (pintype "bidirectional"))
      (node (ref "J2") (pin "4") (pinfunction "ID_4") (pintype "passive"))
    )
    (net (code "208") (name "USB_OTG_FS_PSO") (class "Default")
      (node (ref "IC3") (pin "147") (pinfunction "PD5_147") (pintype "bidirectional"))
      (node (ref "IC8") (pin "4") (pinfunction "EN_4") (pintype "input"))
    )
    (net (code "209") (name "USB_OTG_FS_VBUS") (class "Default")
      (node (ref "C49") (pin "+") (pinfunction "+_+") (pintype "passive"))
      (node (ref "C52") (pin "2") (pinfunction "2_2") (pintype "passive"))
      (node (ref "IC10") (pin "6") (pinfunction "VCC_6") (pintype "passive"))
      (node (ref "IC3") (pin "124") (pinfunction "PA9_124") (pintype "bidirectional"))
      (node (ref "IC8") (pin "1") (pinfunction "OUT_1") (pintype "output"))
      (node (ref "J2") (pin "1") (pinfunction "VCC_1") (pintype "passive"))
      (node (ref "R27") (pin "1") (pinfunction "1_1") (pintype "passive"))
    )
    (net (code "210") (name "USER_SW") (class "Default")
      (node (ref "C4") (pin "2") (pinfunction "2_2") (pintype "passive"))
      (node (ref "IC3") (pin "152") (pinfunction "PG9_152") (pintype "bidirectional"))
      (node (ref "SW1") (pin "1") (pinfunction "1_1") (pintype "passive"))
    )
    (net (code "211") (name "VBAT") (class "Default")
      (node (ref "IC3") (pin "6") (pinfunction "VBAT_6") (pintype "power_in"))
      (node (ref "JP4") (pin "COM") (pinfunction "COM_COM") (pintype "passive"))
    )
    (net (code "212") (name "VCAP1") (class "Default")
      (node (ref "C37") (pin "1") (pinfunction "1_1") (pintype "passive"))
      (node (ref "IC3") (pin "81") (pinfunction "VCAP_1_81") (pintype "power_in"))
    )
    (net (code "213") (name "VCAP2") (class "Default")
      (node (ref "C36") (pin "1") (pinfunction "1_1") (pintype "passive"))
      (node (ref "IC3") (pin "129") (pinfunction "VCAP_2_129") (pintype "power_in"))
    )
    (net (code "214") (name "VDD") (class "Default")
      (node (ref "C16") (pin "1") (pinfunction "1_1") (pintype "passive"))
      (node (ref "C17") (pin "1") (pinfunction "1_1") (pintype "passive"))
      (node (ref "C18") (pin "1") (pinfunction "1_1") (pintype "passive"))
      (node (ref "C19") (pin "1") (pinfunction "1_1") (pintype "passive"))
      (node (ref "C20") (pin "1") (pinfunction "1_1") (pintype "passive"))
      (node (ref "C21") (pin "1") (pinfunction "1_1") (pintype "passive"))
      (node (ref "C22") (pin "+") (pinfunction "+_+") (pintype "passive"))
      (node (ref "C23") (pin "1") (pinfunction "1_1") (pintype "passive"))
      (node (ref "C24") (pin "1") (pinfunction "1_1") (pintype "passive"))
      (node (ref "C25") (pin "1") (pinfunction "1_1") (pintype "passive"))
      (node (ref "C26") (pin "1") (pinfunction "1_1") (pintype "passive"))
      (node (ref "C27") (pin "1") (pinfunction "1_1") (pintype "passive"))
      (node (ref "C28") (pin "1") (pinfunction "1_1") (pintype "passive"))
      (node (ref "C29") (pin "1") (pinfunction "1_1") (pintype "passive"))
      (node (ref "C30") (pin "1") (pinfunction "1_1") (pintype "passive"))
      (node (ref "C31") (pin "1") (pinfunction "1_1") (pintype "passive"))
      (node (ref "C32") (pin "1") (pinfunction "1_1") (pintype "passive"))
      (node (ref "C33") (pin "1") (pinfunction "1_1") (pintype "passive"))
      (node (ref "C8") (pin "2") (pinfunction "2_2") (pintype "passive"))
      (node (ref "FB1") (pin "P$1") (pinfunction "1_P$1") (pintype "passive"))
      (node (ref "IC3") (pin "118") (pinfunction "VDDUSB_118") (pintype "power_in"))
      (node (ref "IC3") (pin "131") (pinfunction "VDD_10_131") (pintype "power_in"))
      (node (ref "IC3") (pin "136") (pinfunction "VDD_11_136") (pintype "power_in"))
      (node (ref "IC3") (pin "149") (pinfunction "VDDSDMMC_149") (pintype "power_in"))
      (node (ref "IC3") (pin "15") (pinfunction "VDD_2_15") (pintype "power_in"))
      (node (ref "IC3") (pin "159") (pinfunction "VDD_12_159") (pintype "power_in"))
      (node (ref "IC3") (pin "171") (pinfunction "PDR_ON_171") (pintype "passive"))
      (node (ref "IC3") (pin "172") (pinfunction "VDD_172") (pintype "power_in"))
      (node (ref "IC3") (pin "23") (pinfunction "VDD_3_23") (pintype "power_in"))
      (node (ref "IC3") (pin "36") (pinfunction "VDD_4_36") (pintype "power_in"))
      (node (ref "IC3") (pin "49") (pinfunction "VDD_5_49") (pintype "power_in"))
      (node (ref "IC3") (pin "62") (pinfunction "VDD_6_62") (pintype "power_in"))
      (node (ref "IC3") (pin "72") (pinfunction "VDD_7_72") (pintype "power_in"))
      (node (ref "IC3") (pin "82") (pinfunction "VDD_8_82") (pintype "power_in"))
      (node (ref "IC3") (pin "96") (pinfunction "VDD_9_96") (pintype "power_in"))
      (node (ref "IC3") (pin "99") (pinfunction "VDDDSI_99") (pintype "power_in"))
      (node (ref "JP2") (pin "1") (pinfunction "1_1") (pintype "passive"))
      (node (ref "JP4") (pin "NO") (pinfunction "NO_NO") (pintype "passive"))
      (node (ref "R11") (pin "1") (pinfunction "1_1") (pintype "passive"))
    )
    (net (code "215") (name "VDDA") (class "Default")
      (node (ref "C34") (pin "1") (pinfunction "1_1") (pintype "passive"))
      (node (ref "C35") (pin "1") (pinfunction "1_1") (pintype "passive"))
      (node (ref "FB1") (pin "P$2") (pinfunction "2_P$2") (pintype "passive"))
      (node (ref "IC3") (pin "39") (pinfunction "VDDA_39") (pintype "power_in"))
      (node (ref "R17") (pin "2") (pinfunction "2_2") (pintype "passive"))
    )
    (net (code "216") (name "VLED+") (class "Default")
      (node (ref "C48") (pin "1") (pinfunction "1_1") (pintype "passive"))
      (node (ref "D2") (pin "C") (pinfunction "C_C") (pintype "passive"))
      (node (ref "LCD1") (pin "2") (pinfunction "VLED+_2") (pintype "power_in"))
      (node (ref "ZD1") (pin "C") (pinfunction "C_C") (pintype "passive"))
    )
    (net (code "217") (name "VLED-") (class "Default")
      (node (ref "IC9") (pin "3") (pinfunction "FB_3") (pintype "input"))
      (node (ref "LCD1") (pin "1") (pinfunction "VLED-_1") (pintype "power_in"))
      (node (ref "R25") (pin "1") (pinfunction "1_1") (pintype "passive"))
      (node (ref "ZD1") (pin "A") (pinfunction "A_A") (pintype "passive"))
    )
    (net (code "218") (name "VREF+") (class "Default")
      (node (ref "IC3") (pin "38") (pinfunction "VREF+_38") (pintype "power_in"))
      (node (ref "R17") (pin "1") (pinfunction "1_1") (pintype "passive"))
    )
    (net (code "219") (name "XL") (class "Default")
      (node (ref "IC11") (pin "4") (pinfunction "IO3_4") (pintype "bidirectional"))
      (node (ref "IC12") (pin "4") (pinfunction "X-_4") (pintype "input"))
      (node (ref "LCD1") (pin "39") (pinfunction "XL_39") (pintype "passive"))
    )
    (net (code "220") (name "XR") (class "Default")
      (node (ref "IC11") (pin "1") (pinfunction "IO1_1") (pintype "bidirectional"))
      (node (ref "IC12") (pin "2") (pinfunction "X+_2") (pintype "input"))
      (node (ref "LCD1") (pin "37") (pinfunction "XR_37") (pintype "passive"))
    )
    (net (code "221") (name "YD") (class "Default")
      (node (ref "IC11") (pin "2") (pinfunction "IO2_2") (pintype "bidirectional"))
      (node (ref "IC12") (pin "5") (pinfunction "Y-_5") (pintype "input"))
      (node (ref "LCD1") (pin "38") (pinfunction "YD_38") (pintype "passive"))
    )
    (net (code "222") (name "YU") (class "Default")
      (node (ref "IC11") (pin "5") (pinfunction "IO4_5") (pintype "bidirectional"))
      (node (ref "IC12") (pin "3") (pinfunction "Y+_3") (pintype "input"))
      (node (ref "LCD1") (pin "40") (pinfunction "YU_40") (pintype "passive"))
    )
    (net (code "223") (name "unconnected-(IC3A-PC10-Pad139)") (class "Default")
      (node (ref "IC3") (pin "139") (pinfunction "PC10_139") (pintype "bidirectional"))
    )
    (net (code "224") (name "unconnected-(IC3A-PD6-Pad150)") (class "Default")
      (node (ref "IC3") (pin "150") (pinfunction "PD6_150") (pintype "bidirectional"))
    )
    (net (code "225") (name "unconnected-(IC3C-DSI_CKN-Pad105)") (class "Default")
      (node (ref "IC3") (pin "105") (pinfunction "DSI_CKN_105") (pintype "bidirectional"))
    )
    (net (code "226") (name "unconnected-(IC3C-DSI_CKP-Pad104)") (class "Default")
      (node (ref "IC3") (pin "104") (pinfunction "DSI_CKP_104") (pintype "bidirectional"))
    )
    (net (code "227") (name "unconnected-(IC3C-DSI_D0N-Pad102)") (class "Default")
      (node (ref "IC3") (pin "102") (pinfunction "DSI_D0N_102") (pintype "bidirectional"))
    )
    (net (code "228") (name "unconnected-(IC3C-DSI_D0P-Pad101)") (class "Default")
      (node (ref "IC3") (pin "101") (pinfunction "DSI_D0P_101") (pintype "bidirectional"))
    )
    (net (code "229") (name "unconnected-(IC3C-DSI_D1N-Pad108)") (class "Default")
      (node (ref "IC3") (pin "108") (pinfunction "DSI_D1N_108") (pintype "bidirectional"))
    )
    (net (code "230") (name "unconnected-(IC3C-DSI_D1P-Pad107)") (class "Default")
      (node (ref "IC3") (pin "107") (pinfunction "DSI_D1P_107") (pintype "bidirectional"))
    )
    (net (code "231") (name "unconnected-(IC3C-PI8-Pad7)") (class "Default")
      (node (ref "IC3") (pin "7") (pinfunction "PI8_7") (pintype "bidirectional"))
    )
    (net (code "232") (name "unconnected-(IC6-A12{slash}NC-36-Pad36)") (class "Default")
      (node (ref "IC6") (pin "36") (pinfunction "A12/NC-36_36") (pintype "passive"))
    )
    (net (code "233") (name "unconnected-(IC6-NC-40-Pad40)") (class "Default")
      (node (ref "IC6") (pin "40") (pinfunction "NC-40_40") (pintype "no_connect"))
    )
    (net (code "234") (name "unconnected-(IC10-IO4-Pad5)") (class "Default")
      (node (ref "IC10") (pin "5") (pinfunction "IO4_5") (pintype "bidirectional"))
    )
    (net (code "235") (name "unconnected-(IC12-AUX-Pad16)") (class "Default")
      (node (ref "IC12") (pin "16") (pinfunction "AUX_16") (pintype "input"))
    )
    (net (code "236") (name "unconnected-(IC14-CLK_OUT-Pad25)") (class "Default")
      (node (ref "IC14") (pin "25") (pinfunction "CLK_OUT_25") (pintype "output"))
    )
    (net (code "237") (name "unconnected-(IC14-TCK-Pad8)") (class "Default")
      (node (ref "IC14") (pin "8") (pinfunction "TCK_8") (pintype "input"))
    )
    (net (code "238") (name "unconnected-(IC14-TDI-Pad12)") (class "Default")
      (node (ref "IC14") (pin "12") (pinfunction "TDI_12") (pintype "input"))
    )
    (net (code "239") (name "unconnected-(IC14-TDO-Pad9)") (class "Default")
      (node (ref "IC14") (pin "9") (pinfunction "TDO_9") (pintype "output"))
    )
    (net (code "240") (name "unconnected-(IC14-TMS-Pad10)") (class "Default")
      (node (ref "IC14") (pin "10") (pinfunction "TMS_10") (pintype "input"))
    )
    (net (code "241") (name "unconnected-(IC14-X2-Pad33)") (class "Default")
      (node (ref "IC14") (pin "33") (pinfunction "X2_33") (pintype "output"))
    )
    (net (code "242") (name "unconnected-(IC14-~{TRST}-Pad11)") (class "Default")
      (node (ref "IC14") (pin "11") (pinfunction "~{TRST}_11") (pintype "input"))
    )
    (net (code "243") (name "unconnected-(J1-CD{slash}DAT3-Pad2)") (class "Default")
      (node (ref "J1") (pin "2") (pinfunction "CD/DAT3_2") (pintype "passive"))
    )
    (net (code "244") (name "unconnected-(J1-DAT1-Pad8)") (class "Default")
      (node (ref "J1") (pin "8") (pinfunction "DAT1_8") (pintype "passive"))
    )
    (net (code "245") (name "unconnected-(J1-DAT2-Pad1)") (class "Default")
      (node (ref "J1") (pin "1") (pinfunction "DAT2_1") (pintype "passive"))
    )
    (net (code "246") (name "unconnected-(LCD1-NC1-Pad35)") (class "Default")
      (node (ref "LCD1") (pin "35") (pinfunction "NC1_35") (pintype "no_connect"))
    )
    (net (code "247") (name "unconnected-(X2I-1-Pad2)") (class "Default")
      (node (ref "X2") (pin "2") (pinfunction "1_2") (pintype "passive"))
    )
    (net (code "248") (name "~{FAULT}") (class "Default")
      (node (ref "IC3") (pin "58") (pinfunction "PB2_58") (pintype "bidirectional"))
      (node (ref "R14") (pin "2") (pinfunction "2_2") (pintype "passive"))
      (node (ref "X1") (pin "8") (pinfunction "1_8") (pintype "passive"))
      (node (ref "X2") (pin "15") (pinfunction "1_15") (pintype "passive"))
    )
    (net (code "249") (name "~{RESET}") (class "Default")
      (node (ref "C8") (pin "1") (pinfunction "1_1") (pintype "passive"))
      (node (ref "IC14") (pin "29") (pinfunction "RESET_N_29") (pintype "input"))
      (node (ref "IC3") (pin "31") (pinfunction "NRST_31") (pintype "bidirectional"))
      (node (ref "IC5") (pin "4") (pinfunction "IO3_4") (pintype "bidirectional"))
      (node (ref "JP7") (pin "NO") (pinfunction "NO_NO") (pintype "passive"))
      (node (ref "R11") (pin "2") (pinfunction "2_2") (pintype "passive"))
      (node (ref "X1") (pin "6") (pinfunction "1_6") (pintype "passive"))
      (node (ref "X4") (pin "5") (pinfunction "S_5") (pintype "passive"))
    )
    (net (code "250") (name "~{USB_OTG_FS_OC}") (class "Default")
      (node (ref "IC3") (pin "146") (pinfunction "PD4_146") (pintype "bidirectional"))
      (node (ref "IC8") (pin "3") (pinfunction "~{OC}_3") (pintype "passive"))
      (node (ref "R26") (pin "1") (pinfunction "1_1") (pintype "passive"))
    )
  )
)
